# axiom_beta_sensor_cmv12000_tht_v0_16_r1_.net
KiCad netlist of a schematic drawn in EAGLE
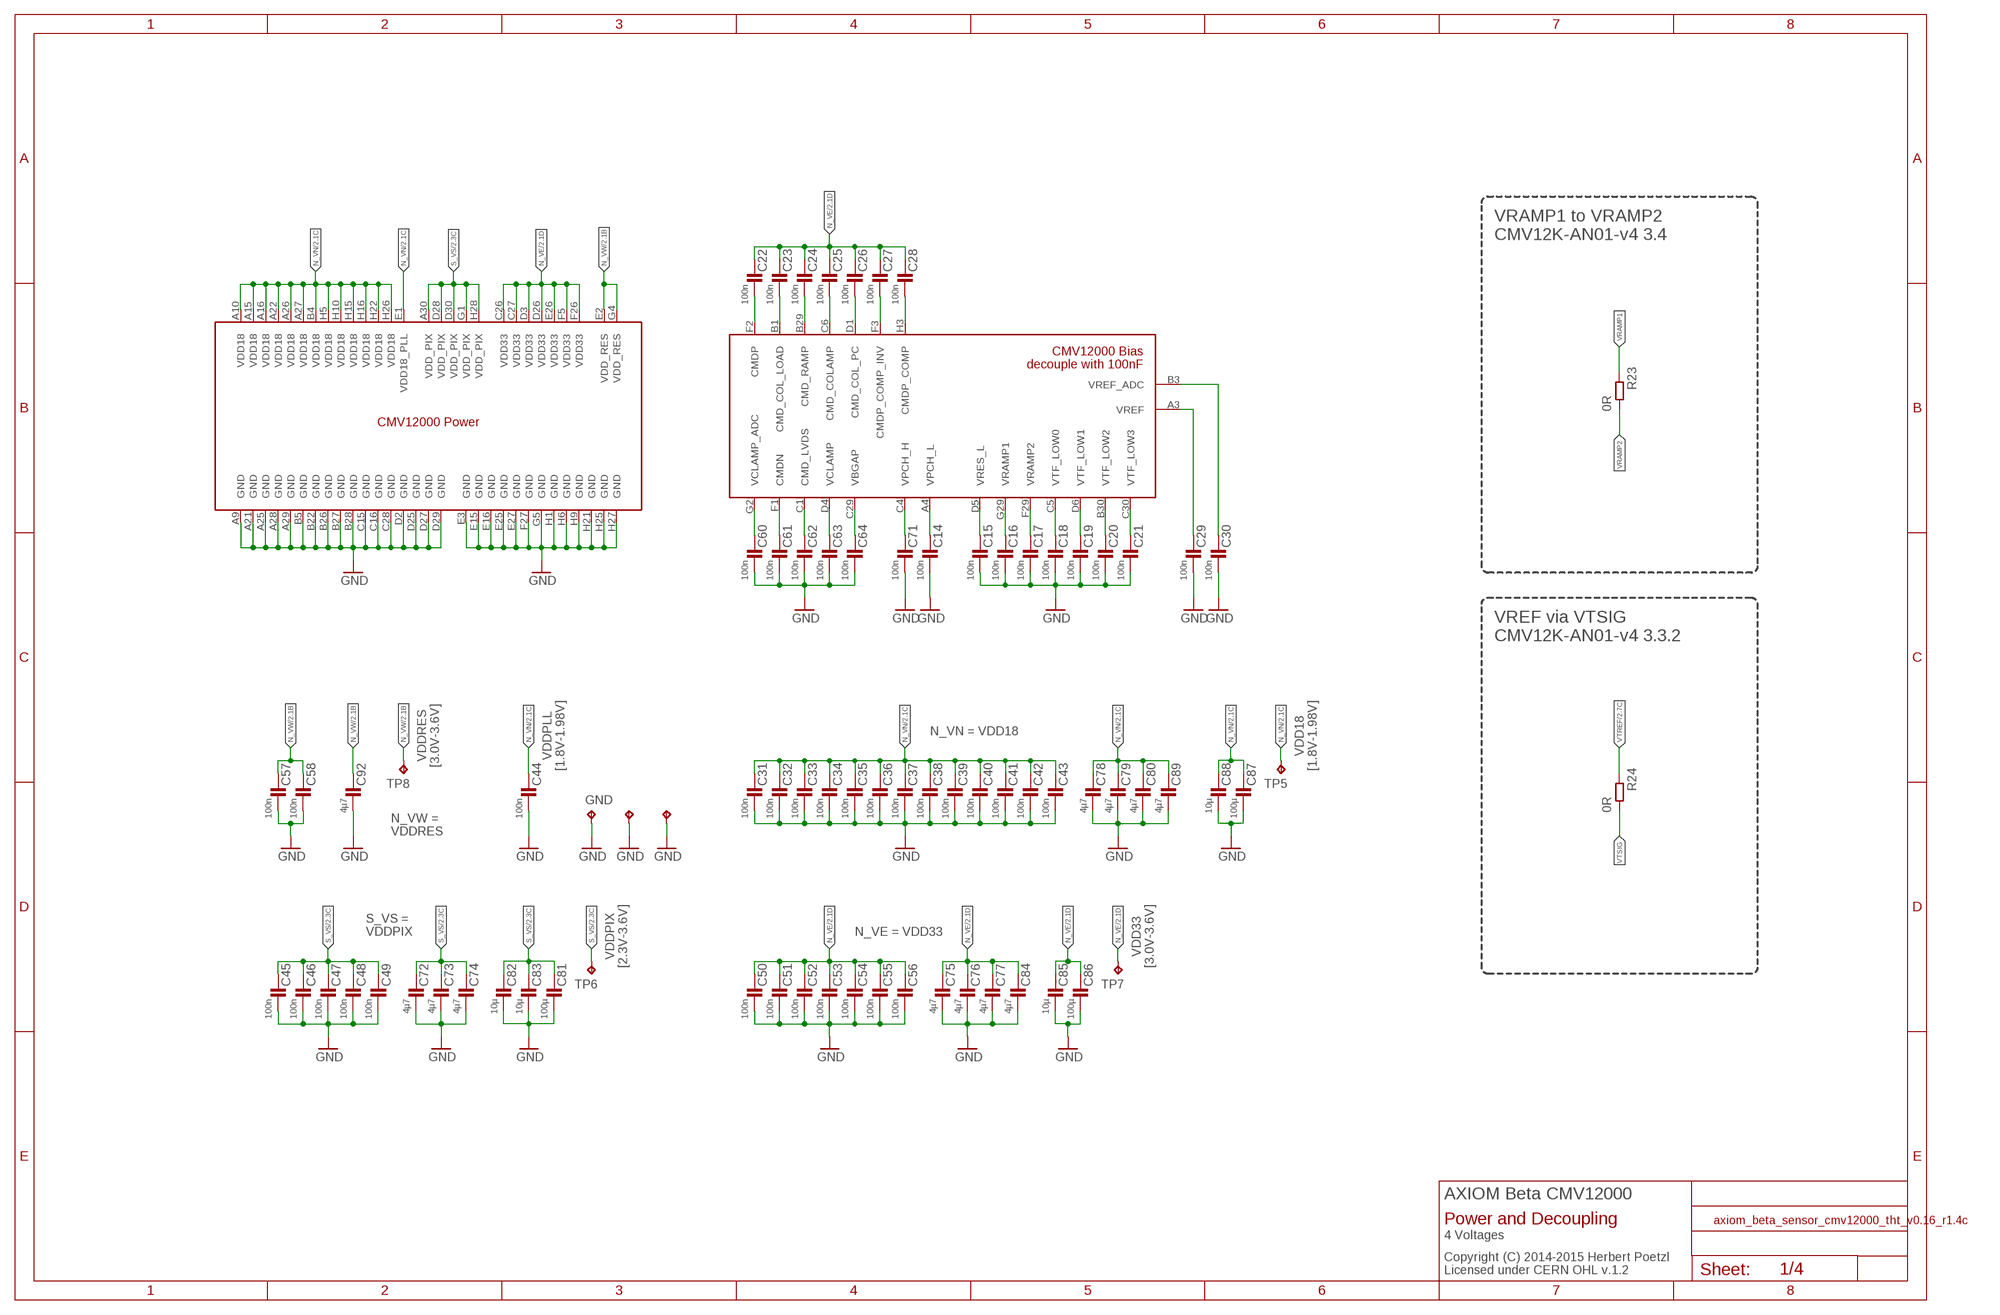
[diagram p0: schematic, sheet 1]
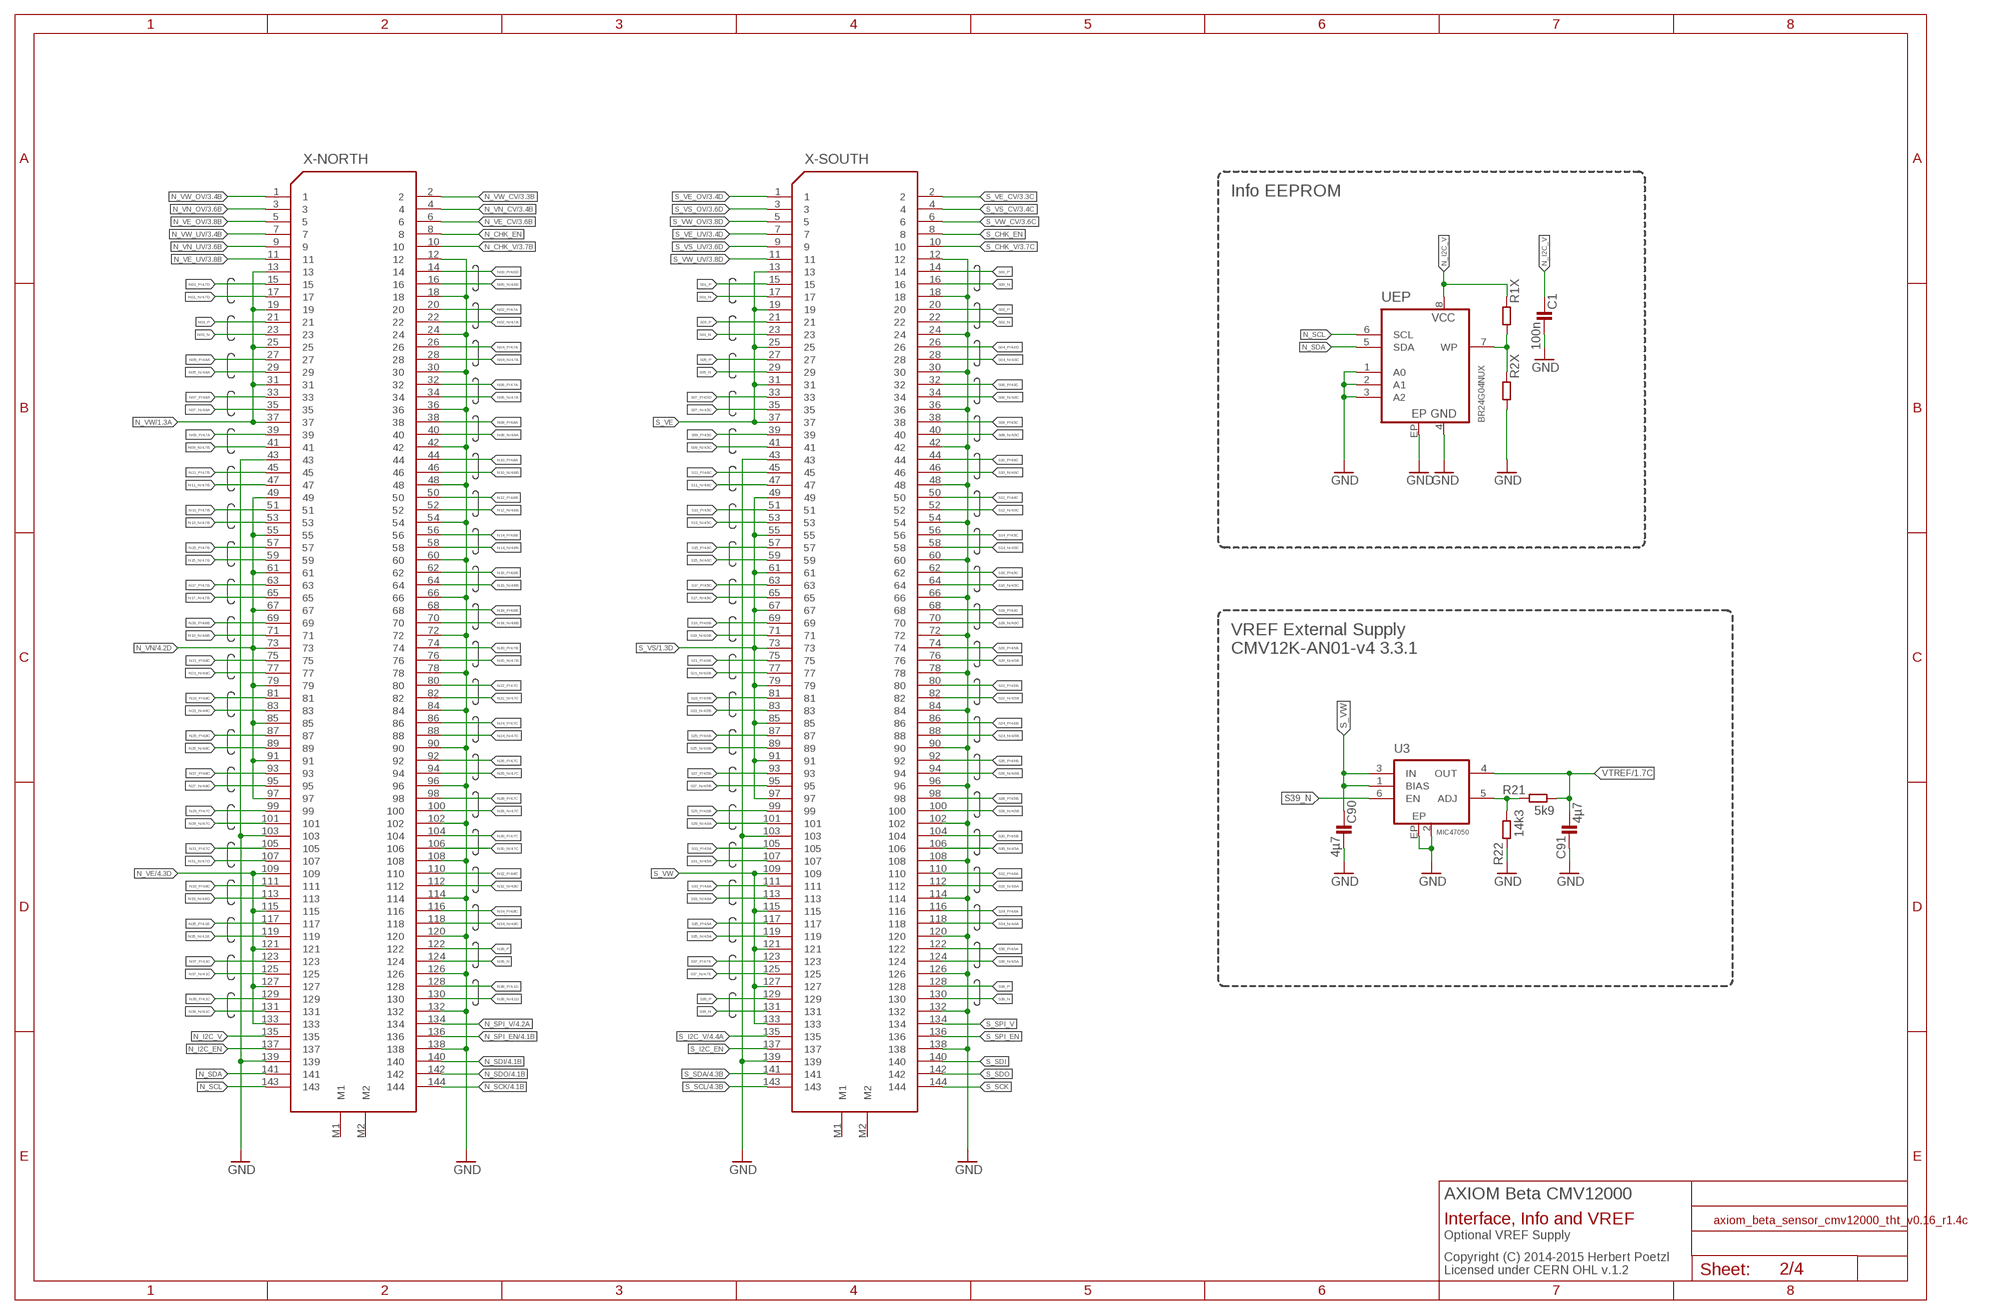
[diagram p1: schematic, sheet 2]
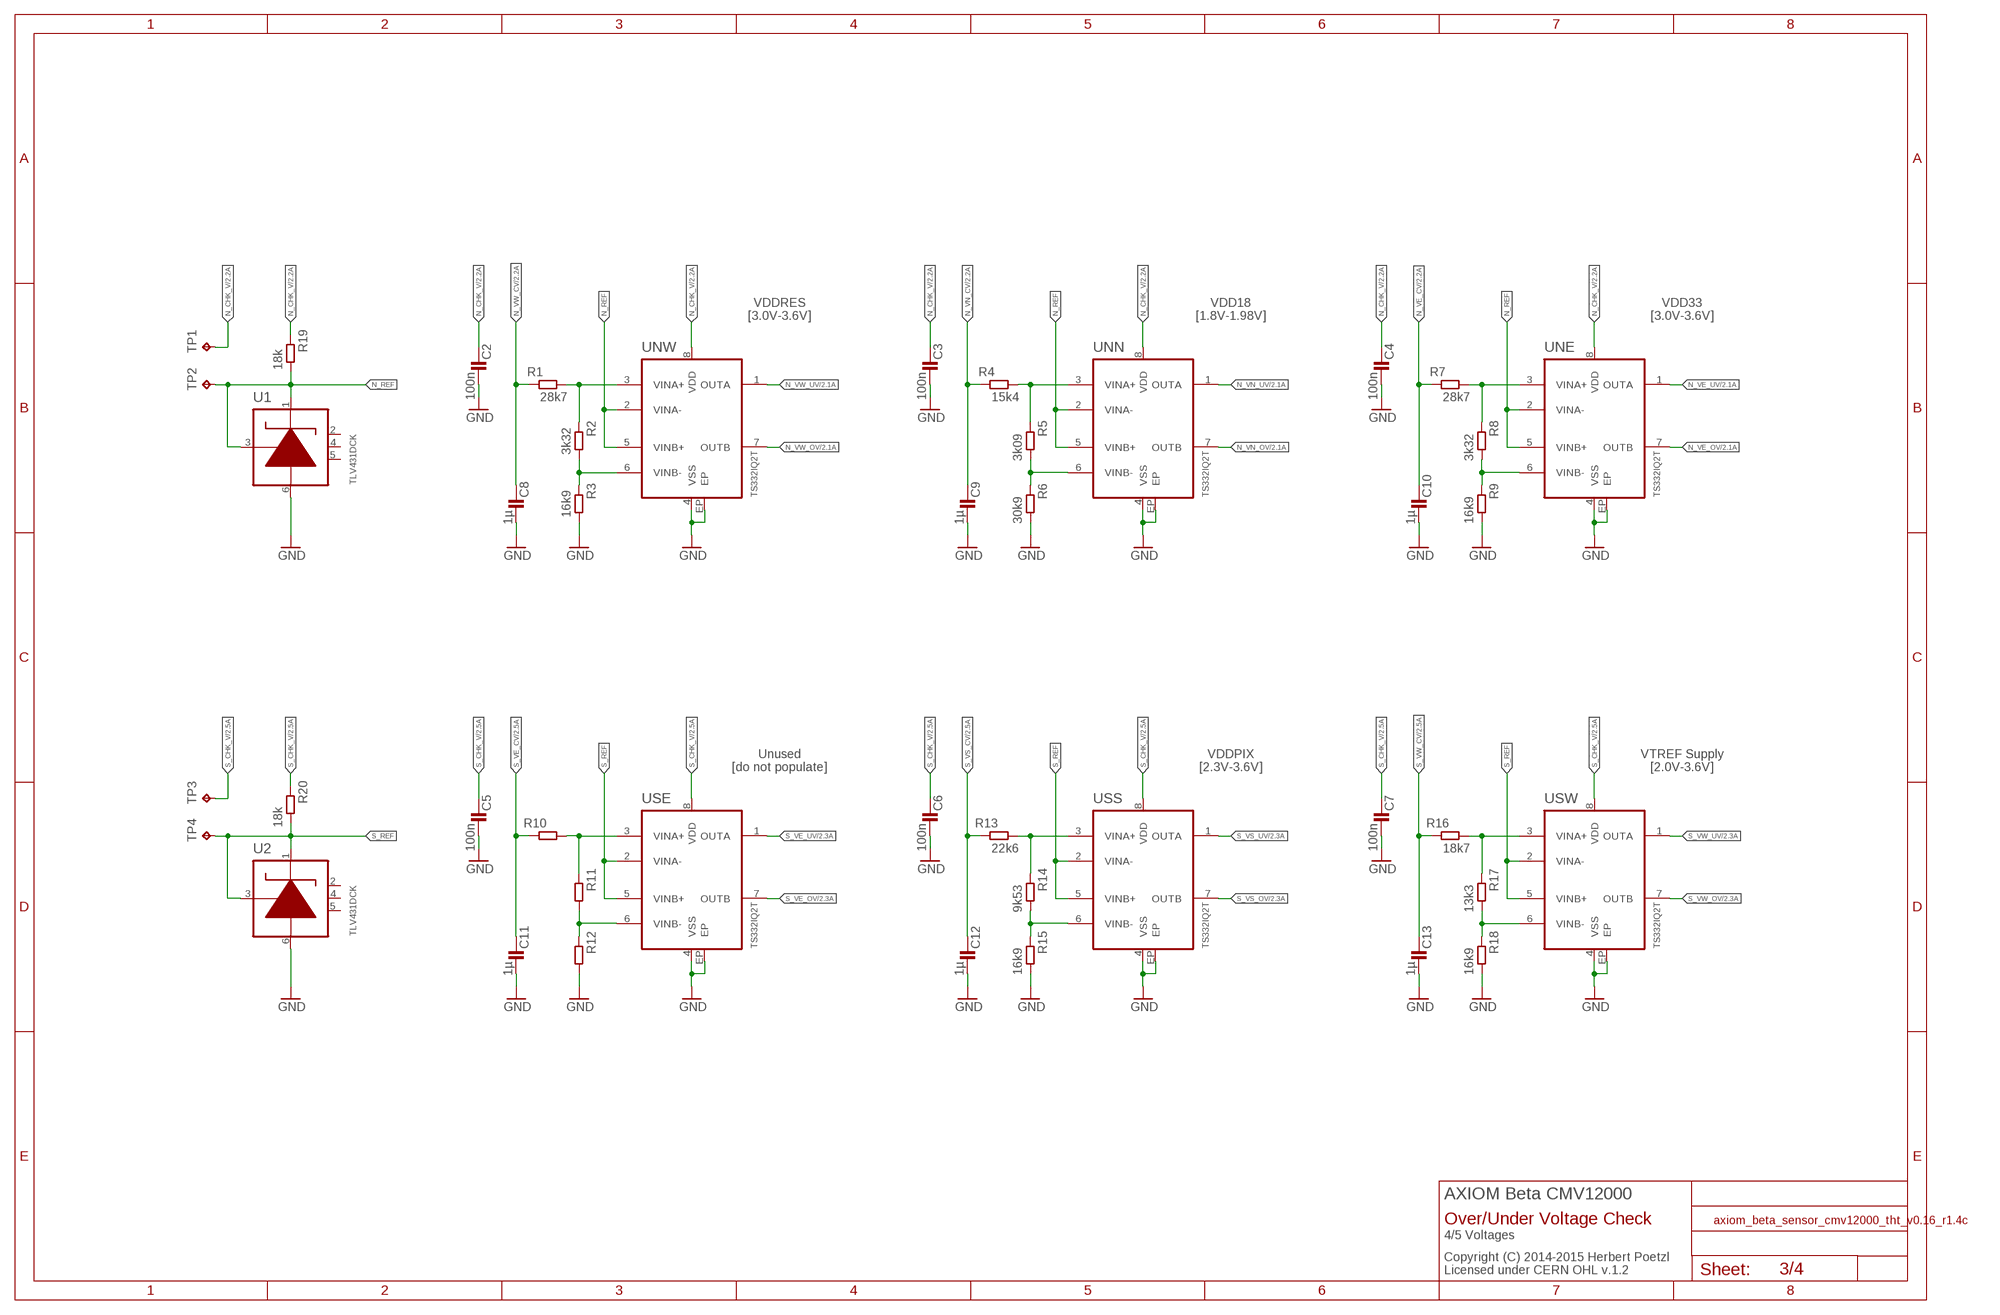
[diagram p2: schematic, sheet 3]
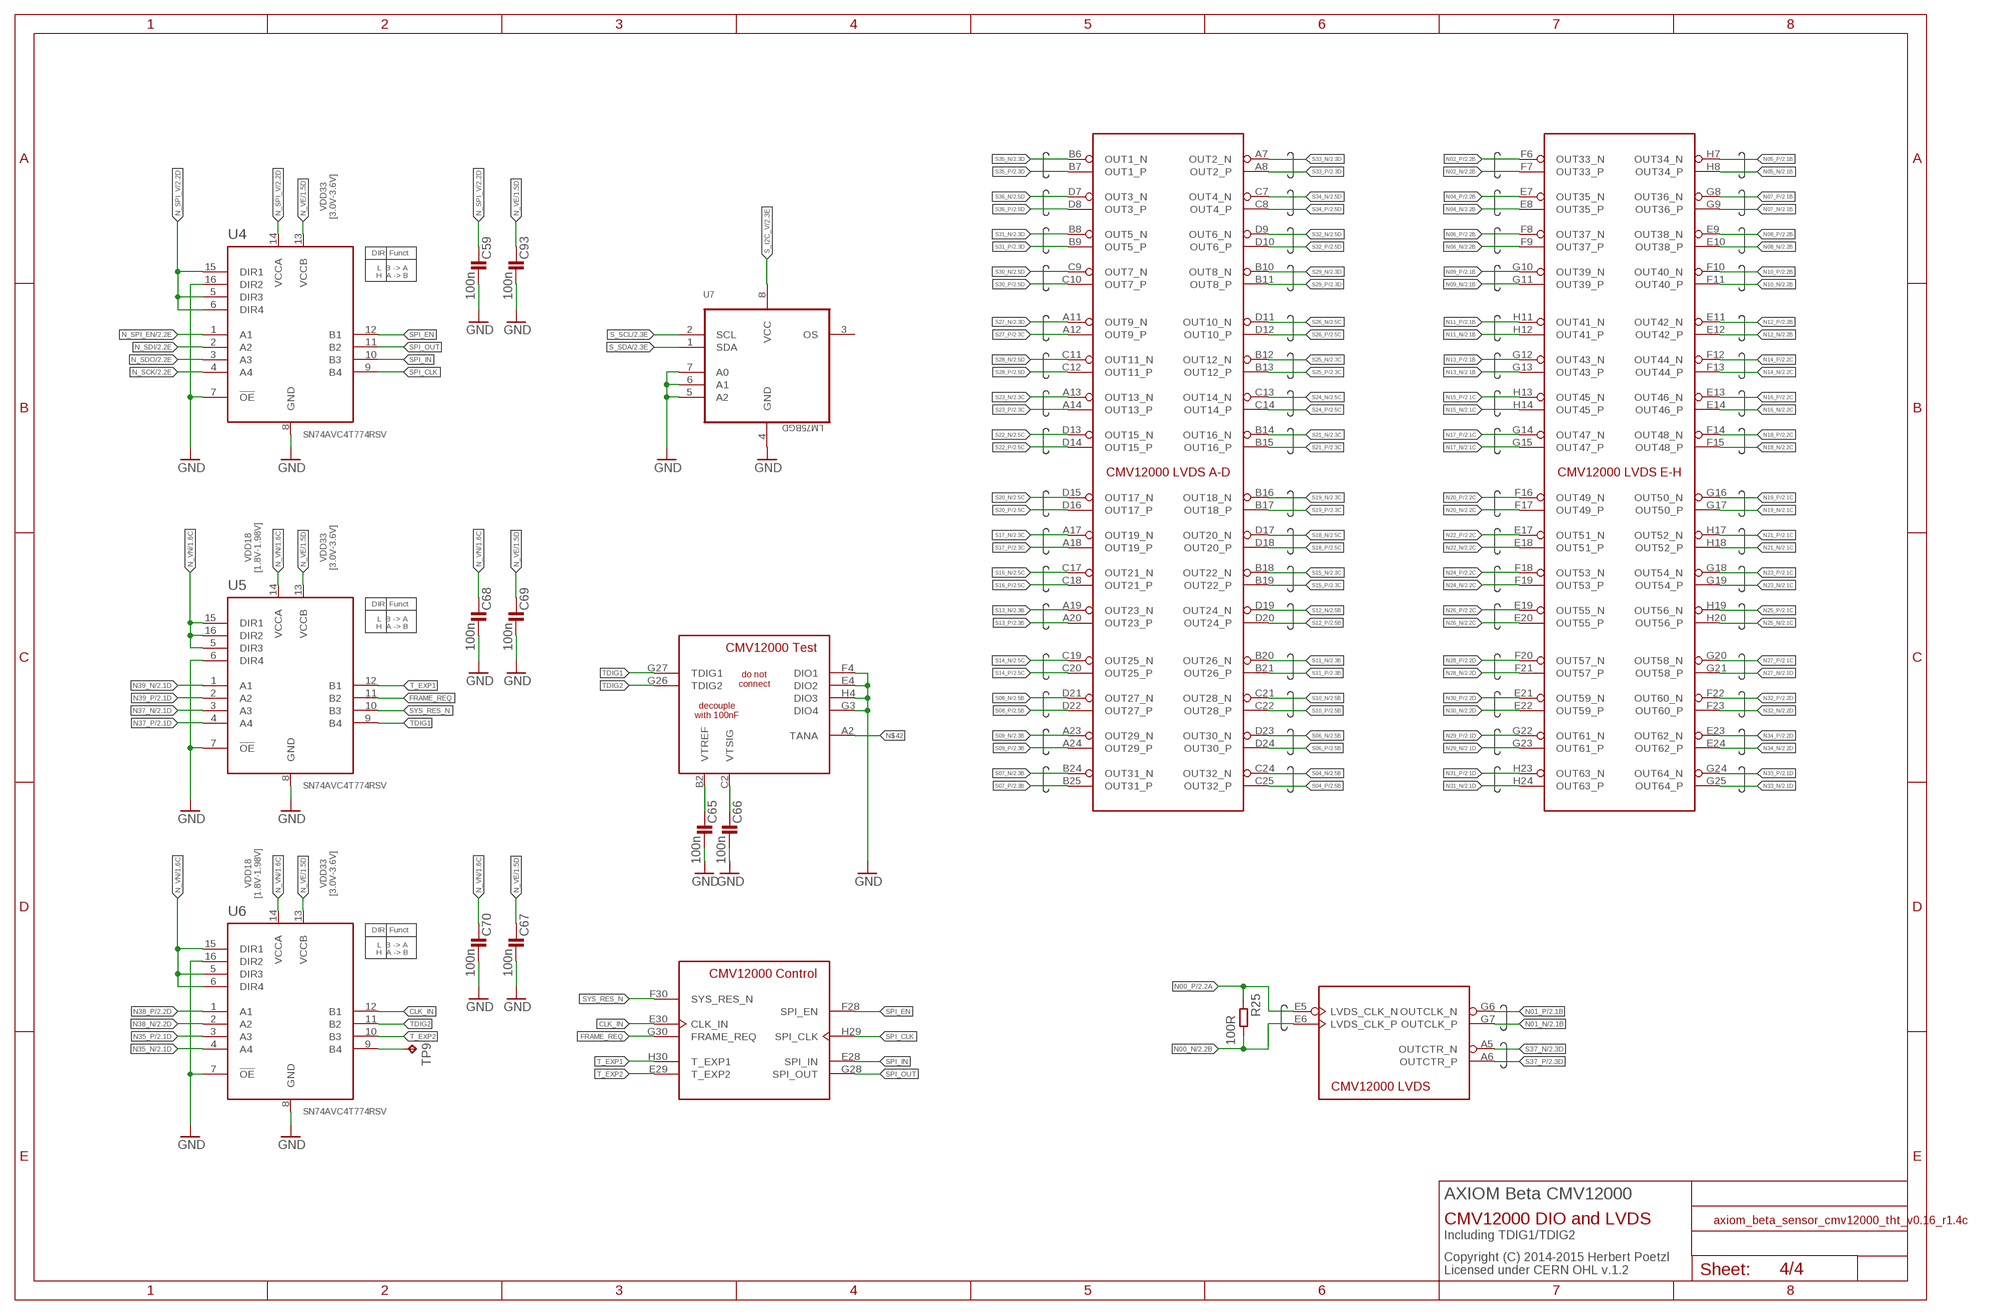
[diagram p3: schematic, sheet 4]

(export (version "E")
  (design (tool "Eeschema 10.0.6"))
  (components
    (comp (ref "C1")
      (value "100n")
      (footprint "eagle-import:0402-C")
      (libsource (lib "eagle-import") (part "C0402-C"))
    )
    (comp (ref "C90")
      (value "4µ7")
      (footprint "eagle-import:0402-C")
      (libsource (lib "eagle-import") (part "C0402-C"))
    )
    (comp (ref "C91")
      (value "4µ7")
      (footprint "eagle-import:0402-C")
      (libsource (lib "eagle-import") (part "C0402-C"))
    )
    (comp (ref "R1X")
      (value "R0402-C")
      (footprint "eagle-import:0402-C")
      (libsource (lib "eagle-import") (part "R0402-C"))
    )
    (comp (ref "R2X")
      (value "R0402-C")
      (footprint "eagle-import:0402-C")
      (libsource (lib "eagle-import") (part "R0402-C"))
    )
    (comp (ref "R21")
      (value "5k9")
      (footprint "eagle-import:0402-C")
      (libsource (lib "eagle-import") (part "R0402-C"))
    )
    (comp (ref "R22")
      (value "14k3")
      (footprint "eagle-import:0402-C")
      (libsource (lib "eagle-import") (part "R0402-C"))
    )
    (comp (ref "U3")
      (value "MIC47050")
      (footprint "eagle-import:MLF-6")
      (libsource (lib "eagle-import") (part "MIC47050-ADJ"))
    )
    (comp (ref "UEP")
      (value "BR24G04NUX")
      (footprint "eagle-import:DFN200X300X100-9N")
      (libsource (lib "eagle-import") (part "BR24G04NUX"))
    )
    (comp (ref "X-NORTH")
      (value "FX10-144P")
      (footprint "eagle-import:FX10A-144P")
      (libsource (lib "eagle-import") (part "FX10-144P"))
    )
    (comp (ref "X-SOUTH")
      (value "FX10-144P")
      (footprint "eagle-import:FX10A-144P")
      (libsource (lib "eagle-import") (part "FX10-144P"))
    )
    (comp (ref "C59")
      (value "100n")
      (footprint "eagle-import:0402-C")
      (libsource (lib "eagle-import") (part "C0402-C"))
    )
    (comp (ref "C65")
      (value "100n")
      (footprint "eagle-import:0402-C")
      (libsource (lib "eagle-import") (part "C0402-C"))
    )
    (comp (ref "C66")
      (value "100n")
      (footprint "eagle-import:0402-C")
      (libsource (lib "eagle-import") (part "C0402-C"))
    )
    (comp (ref "C67")
      (value "100n")
      (footprint "eagle-import:0402-C")
      (libsource (lib "eagle-import") (part "C0402-C"))
    )
    (comp (ref "C68")
      (value "100n")
      (footprint "eagle-import:0402-C")
      (libsource (lib "eagle-import") (part "C0402-C"))
    )
    (comp (ref "C69")
      (value "100n")
      (footprint "eagle-import:0402-C")
      (libsource (lib "eagle-import") (part "C0402-C"))
    )
    (comp (ref "C70")
      (value "100n")
      (footprint "eagle-import:0402-C")
      (libsource (lib "eagle-import") (part "C0402-C"))
    )
    (comp (ref "C93")
      (value "100n")
      (footprint "eagle-import:0402-C")
      (libsource (lib "eagle-import") (part "C0402-C"))
    )
    (comp (ref "R25")
      (value "100R")
      (footprint "eagle-import:0402-C")
      (libsource (lib "eagle-import") (part "R0402-C"))
    )
    (comp (ref "SENSOR")
      (value "CMV12000ANDON")
      (footprint "eagle-import:10-30-07-237-400T4")
      (libsource (lib "eagle-import") (part "CMV12000ANDON"))
    )
    (comp (ref "TP9")
      (value "TPTP10R")
      (footprint "eagle-import:TP10R")
      (libsource (lib "eagle-import") (part "TPTP10R"))
    )
    (comp (ref "U4")
      (value "SN74AVC4T774RSV")
      (footprint "eagle-import:QFN40P185X265X55-16N")
      (libsource (lib "eagle-import") (part "SN74AVC4T774RSV"))
    )
    (comp (ref "U5")
      (value "SN74AVC4T774RSV")
      (footprint "eagle-import:QFN40P185X265X55-16N")
      (libsource (lib "eagle-import") (part "SN74AVC4T774RSV"))
    )
    (comp (ref "U6")
      (value "SN74AVC4T774RSV")
      (footprint "eagle-import:QFN40P185X265X55-16N")
      (libsource (lib "eagle-import") (part "SN74AVC4T774RSV"))
    )
    (comp (ref "U7")
      (value "LM75BGD")
      (footprint "eagle-import:SOT996-2_3")
      (libsource (lib "eagle-import") (part "LM75BGD"))
    )
    (comp (ref "C2")
      (value "100n")
      (footprint "eagle-import:0402-C")
      (libsource (lib "eagle-import") (part "C0402-C"))
    )
    (comp (ref "C3")
      (value "100n")
      (footprint "eagle-import:0402-C")
      (libsource (lib "eagle-import") (part "C0402-C"))
    )
    (comp (ref "C4")
      (value "100n")
      (footprint "eagle-import:0402-C")
      (libsource (lib "eagle-import") (part "C0402-C"))
    )
    (comp (ref "C5")
      (value "100n")
      (footprint "eagle-import:0402-C")
      (libsource (lib "eagle-import") (part "C0402-C"))
    )
    (comp (ref "C6")
      (value "100n")
      (footprint "eagle-import:0402-C")
      (libsource (lib "eagle-import") (part "C0402-C"))
    )
    (comp (ref "C7")
      (value "100n")
      (footprint "eagle-import:0402-C")
      (libsource (lib "eagle-import") (part "C0402-C"))
    )
    (comp (ref "C8")
      (value "1µ")
      (footprint "eagle-import:0402-C")
      (libsource (lib "eagle-import") (part "C0402-C"))
    )
    (comp (ref "C9")
      (value "1µ")
      (footprint "eagle-import:0402-C")
      (libsource (lib "eagle-import") (part "C0402-C"))
    )
    (comp (ref "C10")
      (value "1µ")
      (footprint "eagle-import:0402-C")
      (libsource (lib "eagle-import") (part "C0402-C"))
    )
    (comp (ref "C11")
      (value "1µ")
      (footprint "eagle-import:0402-C")
      (libsource (lib "eagle-import") (part "C0402-C"))
    )
    (comp (ref "C12")
      (value "1µ")
      (footprint "eagle-import:0402-C")
      (libsource (lib "eagle-import") (part "C0402-C"))
    )
    (comp (ref "C13")
      (value "1µ")
      (footprint "eagle-import:0402-C")
      (libsource (lib "eagle-import") (part "C0402-C"))
    )
    (comp (ref "R1")
      (value "28k7")
      (footprint "eagle-import:0402-C")
      (libsource (lib "eagle-import") (part "R0402-C"))
    )
    (comp (ref "R2")
      (value "3k32")
      (footprint "eagle-import:0402-C")
      (libsource (lib "eagle-import") (part "R0402-C"))
    )
    (comp (ref "R3")
      (value "16k9")
      (footprint "eagle-import:0402-C")
      (libsource (lib "eagle-import") (part "R0402-C"))
    )
    (comp (ref "R4")
      (value "15k4")
      (footprint "eagle-import:0402-C")
      (libsource (lib "eagle-import") (part "R0402-C"))
    )
    (comp (ref "R5")
      (value "3k09")
      (footprint "eagle-import:0402-C")
      (libsource (lib "eagle-import") (part "R0402-C"))
    )
    (comp (ref "R6")
      (value "30k9")
      (footprint "eagle-import:0402-C")
      (libsource (lib "eagle-import") (part "R0402-C"))
    )
    (comp (ref "R7")
      (value "28k7")
      (footprint "eagle-import:0402-C")
      (libsource (lib "eagle-import") (part "R0402-C"))
    )
    (comp (ref "R8")
      (value "3k32")
      (footprint "eagle-import:0402-C")
      (libsource (lib "eagle-import") (part "R0402-C"))
    )
    (comp (ref "R9")
      (value "16k9")
      (footprint "eagle-import:0402-C")
      (libsource (lib "eagle-import") (part "R0402-C"))
    )
    (comp (ref "R10")
      (value "R0402-C")
      (footprint "eagle-import:0402-C")
      (libsource (lib "eagle-import") (part "R0402-C"))
    )
    (comp (ref "R11")
      (value "R0402-C")
      (footprint "eagle-import:0402-C")
      (libsource (lib "eagle-import") (part "R0402-C"))
    )
    (comp (ref "R12")
      (value "R0402-C")
      (footprint "eagle-import:0402-C")
      (libsource (lib "eagle-import") (part "R0402-C"))
    )
    (comp (ref "R13")
      (value "22k6")
      (footprint "eagle-import:0402-C")
      (libsource (lib "eagle-import") (part "R0402-C"))
    )
    (comp (ref "R14")
      (value "9k53")
      (footprint "eagle-import:0402-C")
      (libsource (lib "eagle-import") (part "R0402-C"))
    )
    (comp (ref "R15")
      (value "16k9")
      (footprint "eagle-import:0402-C")
      (libsource (lib "eagle-import") (part "R0402-C"))
    )
    (comp (ref "R16")
      (value "18k7")
      (footprint "eagle-import:0402-C")
      (libsource (lib "eagle-import") (part "R0402-C"))
    )
    (comp (ref "R17")
      (value "13k3")
      (footprint "eagle-import:0402-C")
      (libsource (lib "eagle-import") (part "R0402-C"))
    )
    (comp (ref "R18")
      (value "16k9")
      (footprint "eagle-import:0402-C")
      (libsource (lib "eagle-import") (part "R0402-C"))
    )
    (comp (ref "R19")
      (value "18k")
      (footprint "eagle-import:0402-C")
      (libsource (lib "eagle-import") (part "R0402-C"))
    )
    (comp (ref "R20")
      (value "18k")
      (footprint "eagle-import:0402-C")
      (libsource (lib "eagle-import") (part "R0402-C"))
    )
    (comp (ref "TP1")
      (value "TPTP10R")
      (footprint "eagle-import:TP10R")
      (libsource (lib "eagle-import") (part "TPTP10R"))
    )
    (comp (ref "TP2")
      (value "TPTP10R")
      (footprint "eagle-import:TP10R")
      (libsource (lib "eagle-import") (part "TPTP10R"))
    )
    (comp (ref "TP3")
      (value "TPTP10R")
      (footprint "eagle-import:TP10R")
      (libsource (lib "eagle-import") (part "TPTP10R"))
    )
    (comp (ref "TP4")
      (value "TPTP10R")
      (footprint "eagle-import:TP10R")
      (libsource (lib "eagle-import") (part "TPTP10R"))
    )
    (comp (ref "U1")
      (value "TLV431DCK")
      (footprint "eagle-import:SOT65P210X110-6N")
      (libsource (lib "eagle-import") (part "TLV431DCK"))
    )
    (comp (ref "U2")
      (value "TLV431DCK")
      (footprint "eagle-import:SOT65P210X110-6N")
      (libsource (lib "eagle-import") (part "TLV431DCK"))
    )
    (comp (ref "UNE")
      (value "TS332IQ2T")
      (footprint "eagle-import:DFN200X200X100-9N")
      (libsource (lib "eagle-import") (part "TS332IQ2T"))
    )
    (comp (ref "UNN")
      (value "TS332IQ2T")
      (footprint "eagle-import:DFN200X200X100-9N")
      (libsource (lib "eagle-import") (part "TS332IQ2T"))
    )
    (comp (ref "UNW")
      (value "TS332IQ2T")
      (footprint "eagle-import:DFN200X200X100-9N")
      (libsource (lib "eagle-import") (part "TS332IQ2T"))
    )
    (comp (ref "USE")
      (value "TS332IQ2T")
      (footprint "eagle-import:DFN200X200X100-9N")
      (libsource (lib "eagle-import") (part "TS332IQ2T"))
    )
    (comp (ref "USS")
      (value "TS332IQ2T")
      (footprint "eagle-import:DFN200X200X100-9N")
      (libsource (lib "eagle-import") (part "TS332IQ2T"))
    )
    (comp (ref "USW")
      (value "TS332IQ2T")
      (footprint "eagle-import:DFN200X200X100-9N")
      (libsource (lib "eagle-import") (part "TS332IQ2T"))
    )
    (comp (ref "C14")
      (value "100n")
      (footprint "eagle-import:0402-C")
      (libsource (lib "eagle-import") (part "C0402-C"))
    )
    (comp (ref "C15")
      (value "100n")
      (footprint "eagle-import:0402-C")
      (libsource (lib "eagle-import") (part "C0402-C"))
    )
    (comp (ref "C16")
      (value "100n")
      (footprint "eagle-import:0402-C")
      (libsource (lib "eagle-import") (part "C0402-C"))
    )
    (comp (ref "C17")
      (value "100n")
      (footprint "eagle-import:0402-C")
      (libsource (lib "eagle-import") (part "C0402-C"))
    )
    (comp (ref "C18")
      (value "100n")
      (footprint "eagle-import:0402-C")
      (libsource (lib "eagle-import") (part "C0402-C"))
    )
    (comp (ref "C19")
      (value "100n")
      (footprint "eagle-import:0402-C")
      (libsource (lib "eagle-import") (part "C0402-C"))
    )
    (comp (ref "C20")
      (value "100n")
      (footprint "eagle-import:0402-C")
      (libsource (lib "eagle-import") (part "C0402-C"))
    )
    (comp (ref "C21")
      (value "100n")
      (footprint "eagle-import:0402-C")
      (libsource (lib "eagle-import") (part "C0402-C"))
    )
    (comp (ref "C22")
      (value "100n")
      (footprint "eagle-import:0402-C")
      (libsource (lib "eagle-import") (part "C0402-C"))
    )
    (comp (ref "C23")
      (value "100n")
      (footprint "eagle-import:0402-C")
      (libsource (lib "eagle-import") (part "C0402-C"))
    )
    (comp (ref "C24")
      (value "100n")
      (footprint "eagle-import:0402-C")
      (libsource (lib "eagle-import") (part "C0402-C"))
    )
    (comp (ref "C25")
      (value "100n")
      (footprint "eagle-import:0402-C")
      (libsource (lib "eagle-import") (part "C0402-C"))
    )
    (comp (ref "C26")
      (value "100n")
      (footprint "eagle-import:0402-C")
      (libsource (lib "eagle-import") (part "C0402-C"))
    )
    (comp (ref "C27")
      (value "100n")
      (footprint "eagle-import:0402-C")
      (libsource (lib "eagle-import") (part "C0402-C"))
    )
    (comp (ref "C28")
      (value "100n")
      (footprint "eagle-import:0402-C")
      (libsource (lib "eagle-import") (part "C0402-C"))
    )
    (comp (ref "C29")
      (value "100n")
      (footprint "eagle-import:0402-C")
      (libsource (lib "eagle-import") (part "C0402-C"))
    )
    (comp (ref "C30")
      (value "100n")
      (footprint "eagle-import:0402-C")
      (libsource (lib "eagle-import") (part "C0402-C"))
    )
    (comp (ref "C31")
      (value "100n")
      (footprint "eagle-import:0402-C")
      (libsource (lib "eagle-import") (part "C0402-C"))
    )
    (comp (ref "C32")
      (value "100n")
      (footprint "eagle-import:0402-C")
      (libsource (lib "eagle-import") (part "C0402-C"))
    )
    (comp (ref "C33")
      (value "100n")
      (footprint "eagle-import:0402-C")
      (libsource (lib "eagle-import") (part "C0402-C"))
    )
    (comp (ref "C34")
      (value "100n")
      (footprint "eagle-import:0402-C")
      (libsource (lib "eagle-import") (part "C0402-C"))
    )
    (comp (ref "C35")
      (value "100n")
      (footprint "eagle-import:0402-C")
      (libsource (lib "eagle-import") (part "C0402-C"))
    )
    (comp (ref "C36")
      (value "100n")
      (footprint "eagle-import:0402-C")
      (libsource (lib "eagle-import") (part "C0402-C"))
    )
    (comp (ref "C37")
      (value "100n")
      (footprint "eagle-import:0402-C")
      (libsource (lib "eagle-import") (part "C0402-C"))
    )
    (comp (ref "C38")
      (value "100n")
      (footprint "eagle-import:0402-C")
      (libsource (lib "eagle-import") (part "C0402-C"))
    )
    (comp (ref "C39")
      (value "100n")
      (footprint "eagle-import:0402-C")
      (libsource (lib "eagle-import") (part "C0402-C"))
    )
    (comp (ref "C40")
      (value "100n")
      (footprint "eagle-import:0402-C")
      (libsource (lib "eagle-import") (part "C0402-C"))
    )
    (comp (ref "C41")
      (value "100n")
      (footprint "eagle-import:0402-C")
      (libsource (lib "eagle-import") (part "C0402-C"))
    )
    (comp (ref "C42")
      (value "100n")
      (footprint "eagle-import:0402-C")
      (libsource (lib "eagle-import") (part "C0402-C"))
    )
    (comp (ref "C43")
      (value "100n")
      (footprint "eagle-import:0402-C")
      (libsource (lib "eagle-import") (part "C0402-C"))
    )
    (comp (ref "C44")
      (value "100n")
      (footprint "eagle-import:0402-C")
      (libsource (lib "eagle-import") (part "C0402-C"))
    )
    (comp (ref "C45")
      (value "100n")
      (footprint "eagle-import:0402-C")
      (libsource (lib "eagle-import") (part "C0402-C"))
    )
    (comp (ref "C46")
      (value "100n")
      (footprint "eagle-import:0402-C")
      (libsource (lib "eagle-import") (part "C0402-C"))
    )
    (comp (ref "C47")
      (value "100n")
      (footprint "eagle-import:0402-C")
      (libsource (lib "eagle-import") (part "C0402-C"))
    )
    (comp (ref "C48")
      (value "100n")
      (footprint "eagle-import:0402-C")
      (libsource (lib "eagle-import") (part "C0402-C"))
    )
    (comp (ref "C49")
      (value "100n")
      (footprint "eagle-import:0402-C")
      (libsource (lib "eagle-import") (part "C0402-C"))
    )
    (comp (ref "C50")
      (value "100n")
      (footprint "eagle-import:0402-C")
      (libsource (lib "eagle-import") (part "C0402-C"))
    )
    (comp (ref "C51")
      (value "100n")
      (footprint "eagle-import:0402-C")
      (libsource (lib "eagle-import") (part "C0402-C"))
    )
    (comp (ref "C52")
      (value "100n")
      (footprint "eagle-import:0402-C")
      (libsource (lib "eagle-import") (part "C0402-C"))
    )
    (comp (ref "C53")
      (value "100n")
      (footprint "eagle-import:0402-C")
      (libsource (lib "eagle-import") (part "C0402-C"))
    )
    (comp (ref "C54")
      (value "100n")
      (footprint "eagle-import:0402-C")
      (libsource (lib "eagle-import") (part "C0402-C"))
    )
    (comp (ref "C55")
      (value "100n")
      (footprint "eagle-import:0402-C")
      (libsource (lib "eagle-import") (part "C0402-C"))
    )
    (comp (ref "C56")
      (value "100n")
      (footprint "eagle-import:0402-C")
      (libsource (lib "eagle-import") (part "C0402-C"))
    )
    (comp (ref "C57")
      (value "100n")
      (footprint "eagle-import:0402-C")
      (libsource (lib "eagle-import") (part "C0402-C"))
    )
    (comp (ref "C58")
      (value "100n")
      (footprint "eagle-import:0402-C")
      (libsource (lib "eagle-import") (part "C0402-C"))
    )
    (comp (ref "C60")
      (value "100n")
      (footprint "eagle-import:0402-C")
      (libsource (lib "eagle-import") (part "C0402-C"))
    )
    (comp (ref "C61")
      (value "100n")
      (footprint "eagle-import:0402-C")
      (libsource (lib "eagle-import") (part "C0402-C"))
    )
    (comp (ref "C62")
      (value "100n")
      (footprint "eagle-import:0402-C")
      (libsource (lib "eagle-import") (part "C0402-C"))
    )
    (comp (ref "C63")
      (value "100n")
      (footprint "eagle-import:0402-C")
      (libsource (lib "eagle-import") (part "C0402-C"))
    )
    (comp (ref "C64")
      (value "100n")
      (footprint "eagle-import:0402-C")
      (libsource (lib "eagle-import") (part "C0402-C"))
    )
    (comp (ref "C71")
      (value "100n")
      (footprint "eagle-import:0402-C")
      (libsource (lib "eagle-import") (part "C0402-C"))
    )
    (comp (ref "C72")
      (value "4µ7")
      (footprint "eagle-import:0402-B")
      (libsource (lib "eagle-import") (part "C0402-B"))
    )
    (comp (ref "C73")
      (value "4µ7")
      (footprint "eagle-import:0402-C")
      (libsource (lib "eagle-import") (part "C0402-C"))
    )
    (comp (ref "C74")
      (value "4µ7")
      (footprint "eagle-import:0402-C")
      (libsource (lib "eagle-import") (part "C0402-C"))
    )
    (comp (ref "C75")
      (value "4µ7")
      (footprint "eagle-import:0402-C")
      (libsource (lib "eagle-import") (part "C0402-C"))
    )
    (comp (ref "C76")
      (value "4µ7")
      (footprint "eagle-import:0402-C")
      (libsource (lib "eagle-import") (part "C0402-C"))
    )
    (comp (ref "C77")
      (value "4µ7")
      (footprint "eagle-import:0402-B")
      (libsource (lib "eagle-import") (part "C0402-B"))
    )
    (comp (ref "C78")
      (value "4µ7")
      (footprint "eagle-import:0402-B")
      (libsource (lib "eagle-import") (part "C0402-B"))
    )
    (comp (ref "C79")
      (value "4µ7")
      (footprint "eagle-import:0402-C")
      (libsource (lib "eagle-import") (part "C0402-C"))
    )
    (comp (ref "C80")
      (value "4µ7")
      (footprint "eagle-import:0402-C")
      (libsource (lib "eagle-import") (part "C0402-C"))
    )
    (comp (ref "C81")
      (value "100µ")
      (footprint "eagle-import:1206-B")
      (libsource (lib "eagle-import") (part "C1206-B"))
    )
    (comp (ref "C82")
      (value "10µ")
      (footprint "eagle-import:0603-C")
      (libsource (lib "eagle-import") (part "C0603-C"))
    )
    (comp (ref "C83")
      (value "10µ")
      (footprint "eagle-import:0603-C")
      (libsource (lib "eagle-import") (part "C0603-C"))
    )
    (comp (ref "C84")
      (value "4µ7")
      (footprint "eagle-import:0402-C")
      (libsource (lib "eagle-import") (part "C0402-C"))
    )
    (comp (ref "C85")
      (value "10µ")
      (footprint "eagle-import:0603-C")
      (libsource (lib "eagle-import") (part "C0603-C"))
    )
    (comp (ref "C86")
      (value "100µ")
      (footprint "eagle-import:1206-B")
      (libsource (lib "eagle-import") (part "C1206-B"))
    )
    (comp (ref "C87")
      (value "100µ")
      (footprint "eagle-import:1206-B")
      (libsource (lib "eagle-import") (part "C1206-B"))
    )
    (comp (ref "C88")
      (value "10µ")
      (footprint "eagle-import:0603-C")
      (libsource (lib "eagle-import") (part "C0603-C"))
    )
    (comp (ref "C89")
      (value "4µ7")
      (footprint "eagle-import:0402-C")
      (libsource (lib "eagle-import") (part "C0402-C"))
    )
    (comp (ref "C92")
      (value "4µ7")
      (footprint "eagle-import:0402-C")
      (libsource (lib "eagle-import") (part "C0402-C"))
    )
    (comp (ref "GND")
      (value "TPTP10R")
      (footprint "eagle-import:TP10R")
      (libsource (lib "eagle-import") (part "TPTP10R"))
    )
    (comp (ref "GND75")
      (value "TPTP10R")
      (footprint "eagle-import:TP10R")
      (libsource (lib "eagle-import") (part "TPTP10R"))
    )
    (comp (ref "GND77")
      (value "TPTP10R")
      (footprint "eagle-import:TP10R")
      (libsource (lib "eagle-import") (part "TPTP10R"))
    )
    (comp (ref "R23")
      (value "0R")
      (footprint "eagle-import:0402-C")
      (libsource (lib "eagle-import") (part "R0402-C"))
    )
    (comp (ref "R24")
      (value "0R")
      (footprint "eagle-import:0402-C")
      (libsource (lib "eagle-import") (part "R0402-C"))
    )
    (comp (ref "TP5")
      (value "TPTP10R")
      (footprint "eagle-import:TP10R")
      (libsource (lib "eagle-import") (part "TPTP10R"))
    )
    (comp (ref "TP6")
      (value "TPTP10R")
      (footprint "eagle-import:TP10R")
      (libsource (lib "eagle-import") (part "TPTP10R"))
    )
    (comp (ref "TP7")
      (value "TPTP10R")
      (footprint "eagle-import:TP10R")
      (libsource (lib "eagle-import") (part "TPTP10R"))
    )
    (comp (ref "TP8")
      (value "TPTP10R")
      (footprint "eagle-import:TP10R")
      (libsource (lib "eagle-import") (part "TPTP10R"))
    )
  )
  (nets
    (net (code "1") (name "CLK_IN") (class "Default")
      (node (ref "SENSOR") (pin "E30") (pinfunction "CLK_IN_E30") (pintype "input"))
      (node (ref "U6") (pin "12") (pinfunction "B1_12") (pintype "bidirectional"))
    )
    (net (code "2") (name "FRAME_REQ") (class "Default")
      (node (ref "SENSOR") (pin "G30") (pinfunction "FRAME_REQ_G30") (pintype "input"))
      (node (ref "U5") (pin "11") (pinfunction "B2_11") (pintype "bidirectional"))
    )
    (net (code "3") (name "GND") (class "Default")
      (node (ref "C1") (pin "2") (pinfunction "2_2") (pintype "passive"))
      (node (ref "C10") (pin "2") (pinfunction "2_2") (pintype "passive"))
      (node (ref "C11") (pin "2") (pinfunction "2_2") (pintype "passive"))
      (node (ref "C12") (pin "2") (pinfunction "2_2") (pintype "passive"))
      (node (ref "C13") (pin "2") (pinfunction "2_2") (pintype "passive"))
      (node (ref "C14") (pin "2") (pinfunction "2_2") (pintype "passive"))
      (node (ref "C15") (pin "2") (pinfunction "2_2") (pintype "passive"))
      (node (ref "C16") (pin "2") (pinfunction "2_2") (pintype "passive"))
      (node (ref "C17") (pin "2") (pinfunction "2_2") (pintype "passive"))
      (node (ref "C18") (pin "2") (pinfunction "2_2") (pintype "passive"))
      (node (ref "C19") (pin "2") (pinfunction "2_2") (pintype "passive"))
      (node (ref "C2") (pin "2") (pinfunction "2_2") (pintype "passive"))
      (node (ref "C20") (pin "2") (pinfunction "2_2") (pintype "passive"))
      (node (ref "C21") (pin "2") (pinfunction "2_2") (pintype "passive"))
      (node (ref "C29") (pin "2") (pinfunction "2_2") (pintype "passive"))
      (node (ref "C3") (pin "2") (pinfunction "2_2") (pintype "passive"))
      (node (ref "C30") (pin "2") (pinfunction "2_2") (pintype "passive"))
      (node (ref "C31") (pin "2") (pinfunction "2_2") (pintype "passive"))
      (node (ref "C32") (pin "2") (pinfunction "2_2") (pintype "passive"))
      (node (ref "C33") (pin "2") (pinfunction "2_2") (pintype "passive"))
      (node (ref "C34") (pin "2") (pinfunction "2_2") (pintype "passive"))
      (node (ref "C35") (pin "2") (pinfunction "2_2") (pintype "passive"))
      (node (ref "C36") (pin "2") (pinfunction "2_2") (pintype "passive"))
      (node (ref "C37") (pin "2") (pinfunction "2_2") (pintype "passive"))
      (node (ref "C38") (pin "2") (pinfunction "2_2") (pintype "passive"))
      (node (ref "C39") (pin "2") (pinfunction "2_2") (pintype "passive"))
      (node (ref "C4") (pin "2") (pinfunction "2_2") (pintype "passive"))
      (node (ref "C40") (pin "2") (pinfunction "2_2") (pintype "passive"))
      (node (ref "C41") (pin "2") (pinfunction "2_2") (pintype "passive"))
      (node (ref "C42") (pin "2") (pinfunction "2_2") (pintype "passive"))
      (node (ref "C43") (pin "2") (pinfunction "2_2") (pintype "passive"))
      (node (ref "C44") (pin "2") (pinfunction "2_2") (pintype "passive"))
      (node (ref "C45") (pin "2") (pinfunction "2_2") (pintype "passive"))
      (node (ref "C46") (pin "2") (pinfunction "2_2") (pintype "passive"))
      (node (ref "C47") (pin "2") (pinfunction "2_2") (pintype "passive"))
      (node (ref "C48") (pin "2") (pinfunction "2_2") (pintype "passive"))
      (node (ref "C49") (pin "2") (pinfunction "2_2") (pintype "passive"))
      (node (ref "C5") (pin "2") (pinfunction "2_2") (pintype "passive"))
      (node (ref "C50") (pin "2") (pinfunction "2_2") (pintype "passive"))
      (node (ref "C51") (pin "2") (pinfunction "2_2") (pintype "passive"))
      (node (ref "C52") (pin "2") (pinfunction "2_2") (pintype "passive"))
      (node (ref "C53") (pin "2") (pinfunction "2_2") (pintype "passive"))
      (node (ref "C54") (pin "2") (pinfunction "2_2") (pintype "passive"))
      (node (ref "C55") (pin "2") (pinfunction "2_2") (pintype "passive"))
      (node (ref "C56") (pin "2") (pinfunction "2_2") (pintype "passive"))
      (node (ref "C57") (pin "2") (pinfunction "2_2") (pintype "passive"))
      (node (ref "C58") (pin "2") (pinfunction "2_2") (pintype "passive"))
      (node (ref "C59") (pin "2") (pinfunction "2_2") (pintype "passive"))
      (node (ref "C6") (pin "2") (pinfunction "2_2") (pintype "passive"))
      (node (ref "C60") (pin "2") (pinfunction "2_2") (pintype "passive"))
      (node (ref "C61") (pin "2") (pinfunction "2_2") (pintype "passive"))
      (node (ref "C62") (pin "2") (pinfunction "2_2") (pintype "passive"))
      (node (ref "C63") (pin "2") (pinfunction "2_2") (pintype "passive"))
      (node (ref "C64") (pin "2") (pinfunction "2_2") (pintype "passive"))
      (node (ref "C65") (pin "2") (pinfunction "2_2") (pintype "passive"))
      (node (ref "C66") (pin "2") (pinfunction "2_2") (pintype "passive"))
      (node (ref "C67") (pin "2") (pinfunction "2_2") (pintype "passive"))
      (node (ref "C68") (pin "2") (pinfunction "2_2") (pintype "passive"))
      (node (ref "C69") (pin "2") (pinfunction "2_2") (pintype "passive"))
      (node (ref "C7") (pin "2") (pinfunction "2_2") (pintype "passive"))
      (node (ref "C70") (pin "2") (pinfunction "2_2") (pintype "passive"))
      (node (ref "C71") (pin "2") (pinfunction "2_2") (pintype "passive"))
      (node (ref "C72") (pin "2") (pinfunction "2_2") (pintype "passive"))
      (node (ref "C73") (pin "2") (pinfunction "2_2") (pintype "passive"))
      (node (ref "C74") (pin "2") (pinfunction "2_2") (pintype "passive"))
      (node (ref "C75") (pin "2") (pinfunction "2_2") (pintype "passive"))
      (node (ref "C76") (pin "2") (pinfunction "2_2") (pintype "passive"))
      (node (ref "C77") (pin "2") (pinfunction "2_2") (pintype "passive"))
      (node (ref "C78") (pin "2") (pinfunction "2_2") (pintype "passive"))
      (node (ref "C79") (pin "2") (pinfunction "2_2") (pintype "passive"))
      (node (ref "C8") (pin "2") (pinfunction "2_2") (pintype "passive"))
      (node (ref "C80") (pin "2") (pinfunction "2_2") (pintype "passive"))
      (node (ref "C81") (pin "2") (pinfunction "2_2") (pintype "passive"))
      (node (ref "C82") (pin "2") (pinfunction "2_2") (pintype "passive"))
      (node (ref "C83") (pin "2") (pinfunction "2_2") (pintype "passive"))
      (node (ref "C84") (pin "2") (pinfunction "2_2") (pintype "passive"))
      (node (ref "C85") (pin "2") (pinfunction "2_2") (pintype "passive"))
      (node (ref "C86") (pin "2") (pinfunction "2_2") (pintype "passive"))
      (node (ref "C87") (pin "2") (pinfunction "2_2") (pintype "passive"))
      (node (ref "C88") (pin "2") (pinfunction "2_2") (pintype "passive"))
      (node (ref "C89") (pin "2") (pinfunction "2_2") (pintype "passive"))
      (node (ref "C9") (pin "2") (pinfunction "2_2") (pintype "passive"))
      (node (ref "C90") (pin "2") (pinfunction "2_2") (pintype "passive"))
      (node (ref "C91") (pin "1") (pinfunction "1_1") (pintype "passive"))
      (node (ref "C92") (pin "2") (pinfunction "2_2") (pintype "passive"))
      (node (ref "C93") (pin "2") (pinfunction "2_2") (pintype "passive"))
      (node (ref "GND") (pin "TP") (pinfunction "TP_TP") (pintype "input"))
      (node (ref "GND75") (pin "TP") (pinfunction "TP_TP") (pintype "input"))
      (node (ref "GND77") (pin "TP") (pinfunction "TP_TP") (pintype "input"))
      (node (ref "R12") (pin "2") (pinfunction "2_2") (pintype "passive"))
      (node (ref "R15") (pin "2") (pinfunction "2_2") (pintype "passive"))
      (node (ref "R18") (pin "2") (pinfunction "2_2") (pintype "passive"))
      (node (ref "R22") (pin "1") (pinfunction "1_1") (pintype "passive"))
      (node (ref "R2X") (pin "2") (pinfunction "2_2") (pintype "passive"))
      (node (ref "R3") (pin "2") (pinfunction "2_2") (pintype "passive"))
      (node (ref "R6") (pin "2") (pinfunction "2_2") (pintype "passive"))
      (node (ref "R9") (pin "2") (pinfunction "2_2") (pintype "passive"))
      (node (ref "SENSOR") (pin "A21") (pinfunction "GND_A21") (pintype "power_in"))
      (node (ref "SENSOR") (pin "A25") (pinfunction "GND_A25") (pintype "power_in"))
      (node (ref "SENSOR") (pin "A28") (pinfunction "GND_A28") (pintype "power_in"))
      (node (ref "SENSOR") (pin "A29") (pinfunction "GND_A29") (pintype "power_in"))
      (node (ref "SENSOR") (pin "A9") (pinfunction "GND_A9") (pintype "power_in"))
      (node (ref "SENSOR") (pin "B22") (pinfunction "GND_B22") (pintype "power_in"))
      (node (ref "SENSOR") (pin "B26") (pinfunction "GND_B26") (pintype "power_in"))
      (node (ref "SENSOR") (pin "B27") (pinfunction "GND_B27") (pintype "power_in"))
      (node (ref "SENSOR") (pin "B28") (pinfunction "GND_B28") (pintype "power_in"))
      (node (ref "SENSOR") (pin "B5") (pinfunction "GND_B5") (pintype "power_in"))
      (node (ref "SENSOR") (pin "C15") (pinfunction "GND_C15") (pintype "power_in"))
      (node (ref "SENSOR") (pin "C16") (pinfunction "GND_C16") (pintype "power_in"))
      (node (ref "SENSOR") (pin "C28") (pinfunction "GND_C28") (pintype "power_in"))
      (node (ref "SENSOR") (pin "D2") (pinfunction "GND_D2") (pintype "power_in"))
      (node (ref "SENSOR") (pin "D25") (pinfunction "GND_D25") (pintype "power_in"))
      (node (ref "SENSOR") (pin "D27") (pinfunction "GND_D27") (pintype "power_in"))
      (node (ref "SENSOR") (pin "D29") (pinfunction "GND_D29") (pintype "power_in"))
      (node (ref "SENSOR") (pin "E15") (pinfunction "GND_E15") (pintype "power_in"))
      (node (ref "SENSOR") (pin "E16") (pinfunction "GND_E16") (pintype "power_in"))
      (node (ref "SENSOR") (pin "E25") (pinfunction "GND_E25") (pintype "power_in"))
      (node (ref "SENSOR") (pin "E27") (pinfunction "GND_E27") (pintype "power_in"))
      (node (ref "SENSOR") (pin "E3") (pinfunction "GND_E3") (pintype "power_in"))
      (node (ref "SENSOR") (pin "E4") (pinfunction "DIO2_E4") (pintype "output"))
      (node (ref "SENSOR") (pin "F27") (pinfunction "GND_F27") (pintype "power_in"))
      (node (ref "SENSOR") (pin "F4") (pinfunction "DIO1_F4") (pintype "output"))
      (node (ref "SENSOR") (pin "G3") (pinfunction "DIO4_G3") (pintype "output"))
      (node (ref "SENSOR") (pin "G5") (pinfunction "GND_G5") (pintype "power_in"))
      (node (ref "SENSOR") (pin "H1") (pinfunction "GND_H1") (pintype "power_in"))
      (node (ref "SENSOR") (pin "H21") (pinfunction "GND_H21") (pintype "power_in"))
      (node (ref "SENSOR") (pin "H25") (pinfunction "GND_H25") (pintype "power_in"))
      (node (ref "SENSOR") (pin "H27") (pinfunction "GND_H27") (pintype "power_in"))
      (node (ref "SENSOR") (pin "H4") (pinfunction "DIO3_H4") (pintype "output"))
      (node (ref "SENSOR") (pin "H6") (pinfunction "GND_H6") (pintype "power_in"))
      (node (ref "SENSOR") (pin "H9") (pinfunction "GND_H9") (pintype "power_in"))
      (node (ref "U1") (pin "6") (pinfunction "ANODE_6") (pintype "input"))
      (node (ref "U2") (pin "6") (pinfunction "ANODE_6") (pintype "input"))
      (node (ref "U3") (pin "2") (pinfunction "GND_2") (pintype "power_in"))
      (node (ref "U3") (pin "EP") (pinfunction "EP_EP") (pintype "power_in"))
      (node (ref "U4") (pin "16") (pinfunction "DIR2_16") (pintype "input"))
      (node (ref "U4") (pin "7") (pinfunction "~{OE}_7") (pintype "input"))
      (node (ref "U4") (pin "8") (pinfunction "GND_8") (pintype "passive"))
      (node (ref "U5") (pin "6") (pinfunction "DIR4_6") (pintype "input"))
      (node (ref "U5") (pin "7") (pinfunction "~{OE}_7") (pintype "input"))
      (node (ref "U5") (pin "8") (pinfunction "GND_8") (pintype "passive"))
      (node (ref "U6") (pin "16") (pinfunction "DIR2_16") (pintype "input"))
      (node (ref "U6") (pin "7") (pinfunction "~{OE}_7") (pintype "input"))
      (node (ref "U6") (pin "8") (pinfunction "GND_8") (pintype "passive"))
      (node (ref "U7") (pin "4") (pinfunction "GND_4") (pintype "power_in"))
      (node (ref "U7") (pin "5") (pinfunction "A2_5") (pintype "input"))
      (node (ref "U7") (pin "6") (pinfunction "A1_6") (pintype "input"))
      (node (ref "U7") (pin "7") (pinfunction "A0_7") (pintype "input"))
      (node (ref "UEP") (pin "1") (pinfunction "A0_1") (pintype "input"))
      (node (ref "UEP") (pin "2") (pinfunction "A1_2") (pintype "input"))
      (node (ref "UEP") (pin "3") (pinfunction "A2_3") (pintype "input"))
      (node (ref "UEP") (pin "4") (pinfunction "GND_4") (pintype "passive"))
      (node (ref "UEP") (pin "EP") (pinfunction "EP_EP") (pintype "passive"))
      (node (ref "UNE") (pin "4") (pinfunction "VSS_4") (pintype "power_in"))
      (node (ref "UNE") (pin "EP") (pinfunction "EP_EP") (pintype "passive"))
      (node (ref "UNN") (pin "4") (pinfunction "VSS_4") (pintype "power_in"))
      (node (ref "UNN") (pin "EP") (pinfunction "EP_EP") (pintype "passive"))
      (node (ref "UNW") (pin "4") (pinfunction "VSS_4") (pintype "power_in"))
      (node (ref "UNW") (pin "EP") (pinfunction "EP_EP") (pintype "passive"))
      (node (ref "USE") (pin "4") (pinfunction "VSS_4") (pintype "power_in"))
      (node (ref "USE") (pin "EP") (pinfunction "EP_EP") (pintype "passive"))
      (node (ref "USS") (pin "4") (pinfunction "VSS_4") (pintype "power_in"))
      (node (ref "USS") (pin "EP") (pinfunction "EP_EP") (pintype "passive"))
      (node (ref "USW") (pin "4") (pinfunction "VSS_4") (pintype "power_in"))
      (node (ref "USW") (pin "EP") (pinfunction "EP_EP") (pintype "passive"))
      (node (ref "X-NORTH") (pin "102") (pinfunction "102_102") (pintype "bidirectional"))
      (node (ref "X-NORTH") (pin "103") (pinfunction "103_103") (pintype "bidirectional"))
      (node (ref "X-NORTH") (pin "108") (pinfunction "108_108") (pintype "bidirectional"))
      (node (ref "X-NORTH") (pin "114") (pinfunction "114_114") (pintype "bidirectional"))
      (node (ref "X-NORTH") (pin "12") (pinfunction "12_12") (pintype "bidirectional"))
      (node (ref "X-NORTH") (pin "120") (pinfunction "120_120") (pintype "bidirectional"))
      (node (ref "X-NORTH") (pin "126") (pinfunction "126_126") (pintype "bidirectional"))
      (node (ref "X-NORTH") (pin "132") (pinfunction "132_132") (pintype "bidirectional"))
      (node (ref "X-NORTH") (pin "138") (pinfunction "138_138") (pintype "bidirectional"))
      (node (ref "X-NORTH") (pin "139") (pinfunction "139_139") (pintype "bidirectional"))
      (node (ref "X-NORTH") (pin "18") (pinfunction "18_18") (pintype "bidirectional"))
      (node (ref "X-NORTH") (pin "24") (pinfunction "24_24") (pintype "bidirectional"))
      (node (ref "X-NORTH") (pin "30") (pinfunction "30_30") (pintype "bidirectional"))
      (node (ref "X-NORTH") (pin "36") (pinfunction "36_36") (pintype "bidirectional"))
      (node (ref "X-NORTH") (pin "42") (pinfunction "42_42") (pintype "bidirectional"))
      (node (ref "X-NORTH") (pin "43") (pinfunction "43_43") (pintype "bidirectional"))
      (node (ref "X-NORTH") (pin "48") (pinfunction "48_48") (pintype "bidirectional"))
      (node (ref "X-NORTH") (pin "54") (pinfunction "54_54") (pintype "bidirectional"))
      (node (ref "X-NORTH") (pin "60") (pinfunction "60_60") (pintype "bidirectional"))
      (node (ref "X-NORTH") (pin "66") (pinfunction "66_66") (pintype "bidirectional"))
      (node (ref "X-NORTH") (pin "72") (pinfunction "72_72") (pintype "bidirectional"))
      (node (ref "X-NORTH") (pin "78") (pinfunction "78_78") (pintype "bidirectional"))
      (node (ref "X-NORTH") (pin "84") (pinfunction "84_84") (pintype "bidirectional"))
      (node (ref "X-NORTH") (pin "90") (pinfunction "90_90") (pintype "bidirectional"))
      (node (ref "X-NORTH") (pin "96") (pinfunction "96_96") (pintype "bidirectional"))
      (node (ref "X-SOUTH") (pin "102") (pinfunction "102_102") (pintype "bidirectional"))
      (node (ref "X-SOUTH") (pin "103") (pinfunction "103_103") (pintype "bidirectional"))
      (node (ref "X-SOUTH") (pin "108") (pinfunction "108_108") (pintype "bidirectional"))
      (node (ref "X-SOUTH") (pin "114") (pinfunction "114_114") (pintype "bidirectional"))
      (node (ref "X-SOUTH") (pin "12") (pinfunction "12_12") (pintype "bidirectional"))
      (node (ref "X-SOUTH") (pin "120") (pinfunction "120_120") (pintype "bidirectional"))
      (node (ref "X-SOUTH") (pin "126") (pinfunction "126_126") (pintype "bidirectional"))
      (node (ref "X-SOUTH") (pin "132") (pinfunction "132_132") (pintype "bidirectional"))
      (node (ref "X-SOUTH") (pin "138") (pinfunction "138_138") (pintype "bidirectional"))
      (node (ref "X-SOUTH") (pin "139") (pinfunction "139_139") (pintype "bidirectional"))
      (node (ref "X-SOUTH") (pin "18") (pinfunction "18_18") (pintype "bidirectional"))
      (node (ref "X-SOUTH") (pin "24") (pinfunction "24_24") (pintype "bidirectional"))
      (node (ref "X-SOUTH") (pin "30") (pinfunction "30_30") (pintype "bidirectional"))
      (node (ref "X-SOUTH") (pin "36") (pinfunction "36_36") (pintype "bidirectional"))
      (node (ref "X-SOUTH") (pin "42") (pinfunction "42_42") (pintype "bidirectional"))
      (node (ref "X-SOUTH") (pin "43") (pinfunction "43_43") (pintype "bidirectional"))
      (node (ref "X-SOUTH") (pin "48") (pinfunction "48_48") (pintype "bidirectional"))
      (node (ref "X-SOUTH") (pin "54") (pinfunction "54_54") (pintype "bidirectional"))
      (node (ref "X-SOUTH") (pin "60") (pinfunction "60_60") (pintype "bidirectional"))
      (node (ref "X-SOUTH") (pin "66") (pinfunction "66_66") (pintype "bidirectional"))
      (node (ref "X-SOUTH") (pin "72") (pinfunction "72_72") (pintype "bidirectional"))
      (node (ref "X-SOUTH") (pin "78") (pinfunction "78_78") (pintype "bidirectional"))
      (node (ref "X-SOUTH") (pin "84") (pinfunction "84_84") (pintype "bidirectional"))
      (node (ref "X-SOUTH") (pin "90") (pinfunction "90_90") (pintype "bidirectional"))
      (node (ref "X-SOUTH") (pin "96") (pinfunction "96_96") (pintype "bidirectional"))
    )
    (net (code "4") (name "N$42") (class "Default")
      (node (ref "SENSOR") (pin "A2") (pinfunction "TANA_A2") (pintype "output"))
    )
    (net (code "5") (name "N00_N") (class "Default")
      (node (ref "R25") (pin "2") (pinfunction "2_2") (pintype "passive"))
      (node (ref "SENSOR") (pin "E6") (pinfunction "LVDS_CLK_P_E6") (pintype "input"))
      (node (ref "X-NORTH") (pin "16") (pinfunction "16_16") (pintype "bidirectional"))
    )
    (net (code "6") (name "N00_P") (class "Default")
      (node (ref "R25") (pin "1") (pinfunction "1_1") (pintype "passive"))
      (node (ref "SENSOR") (pin "E5") (pinfunction "LVDS_CLK_N_E5") (pintype "input"))
      (node (ref "X-NORTH") (pin "14") (pinfunction "14_14") (pintype "bidirectional"))
    )
    (net (code "7") (name "N01_N") (class "Default")
      (node (ref "SENSOR") (pin "G7") (pinfunction "OUTCLK_P_G7") (pintype "output"))
      (node (ref "X-NORTH") (pin "17") (pinfunction "17_17") (pintype "bidirectional"))
    )
    (net (code "8") (name "N01_P") (class "Default")
      (node (ref "SENSOR") (pin "G6") (pinfunction "OUTCLK_N_G6") (pintype "output"))
      (node (ref "X-NORTH") (pin "15") (pinfunction "15_15") (pintype "bidirectional"))
    )
    (net (code "9") (name "N02_N") (class "Default")
      (node (ref "SENSOR") (pin "F7") (pinfunction "OUT33_P_F7") (pintype "output"))
      (node (ref "X-NORTH") (pin "22") (pinfunction "22_22") (pintype "bidirectional"))
    )
    (net (code "10") (name "N02_P") (class "Default")
      (node (ref "SENSOR") (pin "F6") (pinfunction "OUT33_N_F6") (pintype "output"))
      (node (ref "X-NORTH") (pin "20") (pinfunction "20_20") (pintype "bidirectional"))
    )
    (net (code "11") (name "N03_N") (class "Default")
      (node (ref "X-NORTH") (pin "23") (pinfunction "23_23") (pintype "bidirectional"))
    )
    (net (code "12") (name "N03_P") (class "Default")
      (node (ref "X-NORTH") (pin "21") (pinfunction "21_21") (pintype "bidirectional"))
    )
    (net (code "13") (name "N04_N") (class "Default")
      (node (ref "SENSOR") (pin "E8") (pinfunction "OUT35_P_E8") (pintype "output"))
      (node (ref "X-NORTH") (pin "28") (pinfunction "28_28") (pintype "bidirectional"))
    )
    (net (code "14") (name "N04_P") (class "Default")
      (node (ref "SENSOR") (pin "E7") (pinfunction "OUT35_N_E7") (pintype "output"))
      (node (ref "X-NORTH") (pin "26") (pinfunction "26_26") (pintype "bidirectional"))
    )
    (net (code "15") (name "N05_N") (class "Default")
      (node (ref "SENSOR") (pin "H8") (pinfunction "OUT34_P_H8") (pintype "output"))
      (node (ref "X-NORTH") (pin "29") (pinfunction "29_29") (pintype "bidirectional"))
    )
    (net (code "16") (name "N05_P") (class "Default")
      (node (ref "SENSOR") (pin "H7") (pinfunction "OUT34_N_H7") (pintype "output"))
      (node (ref "X-NORTH") (pin "27") (pinfunction "27_27") (pintype "bidirectional"))
    )
    (net (code "17") (name "N06_N") (class "Default")
      (node (ref "SENSOR") (pin "F9") (pinfunction "OUT37_P_F9") (pintype "output"))
      (node (ref "X-NORTH") (pin "34") (pinfunction "34_34") (pintype "bidirectional"))
    )
    (net (code "18") (name "N06_P") (class "Default")
      (node (ref "SENSOR") (pin "F8") (pinfunction "OUT37_N_F8") (pintype "output"))
      (node (ref "X-NORTH") (pin "32") (pinfunction "32_32") (pintype "bidirectional"))
    )
    (net (code "19") (name "N07_N") (class "Default")
      (node (ref "SENSOR") (pin "G9") (pinfunction "OUT36_P_G9") (pintype "output"))
      (node (ref "X-NORTH") (pin "35") (pinfunction "35_35") (pintype "bidirectional"))
    )
    (net (code "20") (name "N07_P") (class "Default")
      (node (ref "SENSOR") (pin "G8") (pinfunction "OUT36_N_G8") (pintype "output"))
      (node (ref "X-NORTH") (pin "33") (pinfunction "33_33") (pintype "bidirectional"))
    )
    (net (code "21") (name "N08_N") (class "Default")
      (node (ref "SENSOR") (pin "E10") (pinfunction "OUT38_P_E10") (pintype "output"))
      (node (ref "X-NORTH") (pin "40") (pinfunction "40_40") (pintype "bidirectional"))
    )
    (net (code "22") (name "N08_P") (class "Default")
      (node (ref "SENSOR") (pin "E9") (pinfunction "OUT38_N_E9") (pintype "output"))
      (node (ref "X-NORTH") (pin "38") (pinfunction "38_38") (pintype "bidirectional"))
    )
    (net (code "23") (name "N09_N") (class "Default")
      (node (ref "SENSOR") (pin "G11") (pinfunction "OUT39_P_G11") (pintype "output"))
      (node (ref "X-NORTH") (pin "41") (pinfunction "41_41") (pintype "bidirectional"))
    )
    (net (code "24") (name "N09_P") (class "Default")
      (node (ref "SENSOR") (pin "G10") (pinfunction "OUT39_N_G10") (pintype "output"))
      (node (ref "X-NORTH") (pin "39") (pinfunction "39_39") (pintype "bidirectional"))
    )
    (net (code "25") (name "N10_N") (class "Default")
      (node (ref "SENSOR") (pin "F11") (pinfunction "OUT40_P_F11") (pintype "output"))
      (node (ref "X-NORTH") (pin "46") (pinfunction "46_46") (pintype "bidirectional"))
    )
    (net (code "26") (name "N10_P") (class "Default")
      (node (ref "SENSOR") (pin "F10") (pinfunction "OUT40_N_F10") (pintype "output"))
      (node (ref "X-NORTH") (pin "44") (pinfunction "44_44") (pintype "bidirectional"))
    )
    (net (code "27") (name "N11_N") (class "Default")
      (node (ref "SENSOR") (pin "H12") (pinfunction "OUT41_P_H12") (pintype "output"))
      (node (ref "X-NORTH") (pin "47") (pinfunction "47_47") (pintype "bidirectional"))
    )
    (net (code "28") (name "N11_P") (class "Default")
      (node (ref "SENSOR") (pin "H11") (pinfunction "OUT41_N_H11") (pintype "output"))
      (node (ref "X-NORTH") (pin "45") (pinfunction "45_45") (pintype "bidirectional"))
    )
    (net (code "29") (name "N12_N") (class "Default")
      (node (ref "SENSOR") (pin "E12") (pinfunction "OUT42_P_E12") (pintype "output"))
      (node (ref "X-NORTH") (pin "52") (pinfunction "52_52") (pintype "bidirectional"))
    )
    (net (code "30") (name "N12_P") (class "Default")
      (node (ref "SENSOR") (pin "E11") (pinfunction "OUT42_N_E11") (pintype "output"))
      (node (ref "X-NORTH") (pin "50") (pinfunction "50_50") (pintype "bidirectional"))
    )
    (net (code "31") (name "N13_N") (class "Default")
      (node (ref "SENSOR") (pin "G13") (pinfunction "OUT43_P_G13") (pintype "output"))
      (node (ref "X-NORTH") (pin "53") (pinfunction "53_53") (pintype "bidirectional"))
    )
    (net (code "32") (name "N13_P") (class "Default")
      (node (ref "SENSOR") (pin "G12") (pinfunction "OUT43_N_G12") (pintype "output"))
      (node (ref "X-NORTH") (pin "51") (pinfunction "51_51") (pintype "bidirectional"))
    )
    (net (code "33") (name "N14_N") (class "Default")
      (node (ref "SENSOR") (pin "F13") (pinfunction "OUT44_P_F13") (pintype "output"))
      (node (ref "X-NORTH") (pin "58") (pinfunction "58_58") (pintype "bidirectional"))
    )
    (net (code "34") (name "N14_P") (class "Default")
      (node (ref "SENSOR") (pin "F12") (pinfunction "OUT44_N_F12") (pintype "output"))
      (node (ref "X-NORTH") (pin "56") (pinfunction "56_56") (pintype "bidirectional"))
    )
    (net (code "35") (name "N15_N") (class "Default")
      (node (ref "SENSOR") (pin "H14") (pinfunction "OUT45_P_H14") (pintype "output"))
      (node (ref "X-NORTH") (pin "59") (pinfunction "59_59") (pintype "bidirectional"))
    )
    (net (code "36") (name "N15_P") (class "Default")
      (node (ref "SENSOR") (pin "H13") (pinfunction "OUT45_N_H13") (pintype "output"))
      (node (ref "X-NORTH") (pin "57") (pinfunction "57_57") (pintype "bidirectional"))
    )
    (net (code "37") (name "N16_N") (class "Default")
      (node (ref "SENSOR") (pin "E14") (pinfunction "OUT46_P_E14") (pintype "output"))
      (node (ref "X-NORTH") (pin "64") (pinfunction "64_64") (pintype "bidirectional"))
    )
    (net (code "38") (name "N16_P") (class "Default")
      (node (ref "SENSOR") (pin "E13") (pinfunction "OUT46_N_E13") (pintype "output"))
      (node (ref "X-NORTH") (pin "62") (pinfunction "62_62") (pintype "bidirectional"))
    )
    (net (code "39") (name "N17_N") (class "Default")
      (node (ref "SENSOR") (pin "G15") (pinfunction "OUT47_P_G15") (pintype "output"))
      (node (ref "X-NORTH") (pin "65") (pinfunction "65_65") (pintype "bidirectional"))
    )
    (net (code "40") (name "N17_P") (class "Default")
      (node (ref "SENSOR") (pin "G14") (pinfunction "OUT47_N_G14") (pintype "output"))
      (node (ref "X-NORTH") (pin "63") (pinfunction "63_63") (pintype "bidirectional"))
    )
    (net (code "41") (name "N18_N") (class "Default")
      (node (ref "SENSOR") (pin "F15") (pinfunction "OUT48_P_F15") (pintype "output"))
      (node (ref "X-NORTH") (pin "70") (pinfunction "70_70") (pintype "bidirectional"))
    )
    (net (code "42") (name "N18_P") (class "Default")
      (node (ref "SENSOR") (pin "F14") (pinfunction "OUT48_N_F14") (pintype "output"))
      (node (ref "X-NORTH") (pin "68") (pinfunction "68_68") (pintype "bidirectional"))
    )
    (net (code "43") (name "N19_N") (class "Default")
      (node (ref "SENSOR") (pin "G17") (pinfunction "OUT50_P_G17") (pintype "output"))
      (node (ref "X-NORTH") (pin "71") (pinfunction "71_71") (pintype "bidirectional"))
    )
    (net (code "44") (name "N19_P") (class "Default")
      (node (ref "SENSOR") (pin "G16") (pinfunction "OUT50_N_G16") (pintype "output"))
      (node (ref "X-NORTH") (pin "69") (pinfunction "69_69") (pintype "bidirectional"))
    )
    (net (code "45") (name "N20_N") (class "Default")
      (node (ref "SENSOR") (pin "F17") (pinfunction "OUT49_P_F17") (pintype "output"))
      (node (ref "X-NORTH") (pin "76") (pinfunction "76_76") (pintype "bidirectional"))
    )
    (net (code "46") (name "N20_P") (class "Default")
      (node (ref "SENSOR") (pin "F16") (pinfunction "OUT49_N_F16") (pintype "output"))
      (node (ref "X-NORTH") (pin "74") (pinfunction "74_74") (pintype "bidirectional"))
    )
    (net (code "47") (name "N21_N") (class "Default")
      (node (ref "SENSOR") (pin "H18") (pinfunction "OUT52_P_H18") (pintype "output"))
      (node (ref "X-NORTH") (pin "77") (pinfunction "77_77") (pintype "bidirectional"))
    )
    (net (code "48") (name "N21_P") (class "Default")
      (node (ref "SENSOR") (pin "H17") (pinfunction "OUT52_N_H17") (pintype "output"))
      (node (ref "X-NORTH") (pin "75") (pinfunction "75_75") (pintype "bidirectional"))
    )
    (net (code "49") (name "N22_N") (class "Default")
      (node (ref "SENSOR") (pin "E18") (pinfunction "OUT51_P_E18") (pintype "output"))
      (node (ref "X-NORTH") (pin "82") (pinfunction "82_82") (pintype "bidirectional"))
    )
    (net (code "50") (name "N22_P") (class "Default")
      (node (ref "SENSOR") (pin "E17") (pinfunction "OUT51_N_E17") (pintype "output"))
      (node (ref "X-NORTH") (pin "80") (pinfunction "80_80") (pintype "bidirectional"))
    )
    (net (code "51") (name "N23_N") (class "Default")
      (node (ref "SENSOR") (pin "G19") (pinfunction "OUT54_P_G19") (pintype "output"))
      (node (ref "X-NORTH") (pin "83") (pinfunction "83_83") (pintype "bidirectional"))
    )
    (net (code "52") (name "N23_P") (class "Default")
      (node (ref "SENSOR") (pin "G18") (pinfunction "OUT54_N_G18") (pintype "output"))
      (node (ref "X-NORTH") (pin "81") (pinfunction "81_81") (pintype "bidirectional"))
    )
    (net (code "53") (name "N24_N") (class "Default")
      (node (ref "SENSOR") (pin "F19") (pinfunction "OUT53_P_F19") (pintype "output"))
      (node (ref "X-NORTH") (pin "88") (pinfunction "88_88") (pintype "bidirectional"))
    )
    (net (code "54") (name "N24_P") (class "Default")
      (node (ref "SENSOR") (pin "F18") (pinfunction "OUT53_N_F18") (pintype "output"))
      (node (ref "X-NORTH") (pin "86") (pinfunction "86_86") (pintype "bidirectional"))
    )
    (net (code "55") (name "N25_N") (class "Default")
      (node (ref "SENSOR") (pin "H20") (pinfunction "OUT56_P_H20") (pintype "output"))
      (node (ref "X-NORTH") (pin "89") (pinfunction "89_89") (pintype "bidirectional"))
    )
    (net (code "56") (name "N25_P") (class "Default")
      (node (ref "SENSOR") (pin "H19") (pinfunction "OUT56_N_H19") (pintype "output"))
      (node (ref "X-NORTH") (pin "87") (pinfunction "87_87") (pintype "bidirectional"))
    )
    (net (code "57") (name "N26_N") (class "Default")
      (node (ref "SENSOR") (pin "E20") (pinfunction "OUT55_P_E20") (pintype "output"))
      (node (ref "X-NORTH") (pin "94") (pinfunction "94_94") (pintype "bidirectional"))
    )
    (net (code "58") (name "N26_P") (class "Default")
      (node (ref "SENSOR") (pin "E19") (pinfunction "OUT55_N_E19") (pintype "output"))
      (node (ref "X-NORTH") (pin "92") (pinfunction "92_92") (pintype "bidirectional"))
    )
    (net (code "59") (name "N27_N") (class "Default")
      (node (ref "SENSOR") (pin "G21") (pinfunction "OUT58_P_G21") (pintype "output"))
      (node (ref "X-NORTH") (pin "95") (pinfunction "95_95") (pintype "bidirectional"))
    )
    (net (code "60") (name "N27_P") (class "Default")
      (node (ref "SENSOR") (pin "G20") (pinfunction "OUT58_N_G20") (pintype "output"))
      (node (ref "X-NORTH") (pin "93") (pinfunction "93_93") (pintype "bidirectional"))
    )
    (net (code "61") (name "N28_N") (class "Default")
      (node (ref "SENSOR") (pin "F21") (pinfunction "OUT57_P_F21") (pintype "output"))
      (node (ref "X-NORTH") (pin "100") (pinfunction "100_100") (pintype "bidirectional"))
    )
    (net (code "62") (name "N28_P") (class "Default")
      (node (ref "SENSOR") (pin "F20") (pinfunction "OUT57_N_F20") (pintype "output"))
      (node (ref "X-NORTH") (pin "98") (pinfunction "98_98") (pintype "bidirectional"))
    )
    (net (code "63") (name "N29_N") (class "Default")
      (node (ref "SENSOR") (pin "G23") (pinfunction "OUT61_P_G23") (pintype "output"))
      (node (ref "X-NORTH") (pin "101") (pinfunction "101_101") (pintype "bidirectional"))
    )
    (net (code "64") (name "N29_P") (class "Default")
      (node (ref "SENSOR") (pin "G22") (pinfunction "OUT61_N_G22") (pintype "output"))
      (node (ref "X-NORTH") (pin "99") (pinfunction "99_99") (pintype "bidirectional"))
    )
    (net (code "65") (name "N30_N") (class "Default")
      (node (ref "SENSOR") (pin "E22") (pinfunction "OUT59_P_E22") (pintype "output"))
      (node (ref "X-NORTH") (pin "106") (pinfunction "106_106") (pintype "bidirectional"))
    )
    (net (code "66") (name "N30_P") (class "Default")
      (node (ref "SENSOR") (pin "E21") (pinfunction "OUT59_N_E21") (pintype "output"))
      (node (ref "X-NORTH") (pin "104") (pinfunction "104_104") (pintype "bidirectional"))
    )
    (net (code "67") (name "N31_N") (class "Default")
      (node (ref "SENSOR") (pin "H24") (pinfunction "OUT63_P_H24") (pintype "output"))
      (node (ref "X-NORTH") (pin "107") (pinfunction "107_107") (pintype "bidirectional"))
    )
    (net (code "68") (name "N31_P") (class "Default")
      (node (ref "SENSOR") (pin "H23") (pinfunction "OUT63_N_H23") (pintype "output"))
      (node (ref "X-NORTH") (pin "105") (pinfunction "105_105") (pintype "bidirectional"))
    )
    (net (code "69") (name "N32_N") (class "Default")
      (node (ref "SENSOR") (pin "F23") (pinfunction "OUT60_P_F23") (pintype "output"))
      (node (ref "X-NORTH") (pin "112") (pinfunction "112_112") (pintype "bidirectional"))
    )
    (net (code "70") (name "N32_P") (class "Default")
      (node (ref "SENSOR") (pin "F22") (pinfunction "OUT60_N_F22") (pintype "output"))
      (node (ref "X-NORTH") (pin "110") (pinfunction "110_110") (pintype "bidirectional"))
    )
    (net (code "71") (name "N33_N") (class "Default")
      (node (ref "SENSOR") (pin "G25") (pinfunction "OUT64_P_G25") (pintype "output"))
      (node (ref "X-NORTH") (pin "113") (pinfunction "113_113") (pintype "bidirectional"))
    )
    (net (code "72") (name "N33_P") (class "Default")
      (node (ref "SENSOR") (pin "G24") (pinfunction "OUT64_N_G24") (pintype "output"))
      (node (ref "X-NORTH") (pin "111") (pinfunction "111_111") (pintype "bidirectional"))
    )
    (net (code "73") (name "N34_N") (class "Default")
      (node (ref "SENSOR") (pin "E24") (pinfunction "OUT62_P_E24") (pintype "output"))
      (node (ref "X-NORTH") (pin "118") (pinfunction "118_118") (pintype "bidirectional"))
    )
    (net (code "74") (name "N34_P") (class "Default")
      (node (ref "SENSOR") (pin "E23") (pinfunction "OUT62_N_E23") (pintype "output"))
      (node (ref "X-NORTH") (pin "116") (pinfunction "116_116") (pintype "bidirectional"))
    )
    (net (code "75") (name "N35_N") (class "Default")
      (node (ref "U6") (pin "4") (pinfunction "A4_4") (pintype "bidirectional"))
      (node (ref "X-NORTH") (pin "119") (pinfunction "119_119") (pintype "bidirectional"))
    )
    (net (code "76") (name "N35_P") (class "Default")
      (node (ref "U6") (pin "3") (pinfunction "A3_3") (pintype "bidirectional"))
      (node (ref "X-NORTH") (pin "117") (pinfunction "117_117") (pintype "bidirectional"))
    )
    (net (code "77") (name "N36_N") (class "Default")
      (node (ref "X-NORTH") (pin "124") (pinfunction "124_124") (pintype "bidirectional"))
    )
    (net (code "78") (name "N36_P") (class "Default")
      (node (ref "X-NORTH") (pin "122") (pinfunction "122_122") (pintype "bidirectional"))
    )
    (net (code "79") (name "N37_N") (class "Default")
      (node (ref "U5") (pin "3") (pinfunction "A3_3") (pintype "bidirectional"))
      (node (ref "X-NORTH") (pin "125") (pinfunction "125_125") (pintype "bidirectional"))
    )
    (net (code "80") (name "N37_P") (class "Default")
      (node (ref "U5") (pin "4") (pinfunction "A4_4") (pintype "bidirectional"))
      (node (ref "X-NORTH") (pin "123") (pinfunction "123_123") (pintype "bidirectional"))
    )
    (net (code "81") (name "N38_N") (class "Default")
      (node (ref "U6") (pin "2") (pinfunction "A2_2") (pintype "bidirectional"))
      (node (ref "X-NORTH") (pin "130") (pinfunction "130_130") (pintype "bidirectional"))
    )
    (net (code "82") (name "N38_P") (class "Default")
      (node (ref "U6") (pin "1") (pinfunction "A1_1") (pintype "bidirectional"))
      (node (ref "X-NORTH") (pin "128") (pinfunction "128_128") (pintype "bidirectional"))
    )
    (net (code "83") (name "N39_N") (class "Default")
      (node (ref "U5") (pin "1") (pinfunction "A1_1") (pintype "bidirectional"))
      (node (ref "X-NORTH") (pin "131") (pinfunction "131_131") (pintype "bidirectional"))
    )
    (net (code "84") (name "N39_P") (class "Default")
      (node (ref "U5") (pin "2") (pinfunction "A2_2") (pintype "bidirectional"))
      (node (ref "X-NORTH") (pin "129") (pinfunction "129_129") (pintype "bidirectional"))
    )
    (net (code "85") (name "N_CHK_EN") (class "Default")
      (node (ref "X-NORTH") (pin "8") (pinfunction "8_8") (pintype "bidirectional"))
    )
    (net (code "86") (name "N_CHK_V") (class "Default")
      (node (ref "C2") (pin "1") (pinfunction "1_1") (pintype "passive"))
      (node (ref "C3") (pin "1") (pinfunction "1_1") (pintype "passive"))
      (node (ref "C4") (pin "1") (pinfunction "1_1") (pintype "passive"))
      (node (ref "R19") (pin "1") (pinfunction "1_1") (pintype "passive"))
      (node (ref "TP1") (pin "TP") (pinfunction "TP_TP") (pintype "input"))
      (node (ref "UNE") (pin "8") (pinfunction "VDD_8") (pintype "power_in"))
      (node (ref "UNN") (pin "8") (pinfunction "VDD_8") (pintype "power_in"))
      (node (ref "UNW") (pin "8") (pinfunction "VDD_8") (pintype "power_in"))
      (node (ref "X-NORTH") (pin "10") (pinfunction "10_10") (pintype "bidirectional"))
    )
    (net (code "87") (name "N_I2C_EN") (class "Default")
      (node (ref "X-NORTH") (pin "137") (pinfunction "137_137") (pintype "bidirectional"))
    )
    (net (code "88") (name "N_I2C_V") (class "Default")
      (node (ref "C1") (pin "1") (pinfunction "1_1") (pintype "passive"))
      (node (ref "R1X") (pin "1") (pinfunction "1_1") (pintype "passive"))
      (node (ref "UEP") (pin "8") (pinfunction "VCC_8") (pintype "power_in"))
      (node (ref "X-NORTH") (pin "135") (pinfunction "135_135") (pintype "bidirectional"))
    )
    (net (code "89") (name "N_REF") (class "Default")
      (node (ref "R19") (pin "2") (pinfunction "2_2") (pintype "passive"))
      (node (ref "TP2") (pin "TP") (pinfunction "TP_TP") (pintype "input"))
      (node (ref "U1") (pin "1") (pinfunction "CATHODE_1") (pintype "output"))
      (node (ref "U1") (pin "3") (pinfunction "REF_3") (pintype "input"))
      (node (ref "UNE") (pin "2") (pinfunction "VINA-_2") (pintype "input"))
      (node (ref "UNE") (pin "5") (pinfunction "VINB+_5") (pintype "input"))
      (node (ref "UNN") (pin "2") (pinfunction "VINA-_2") (pintype "input"))
      (node (ref "UNN") (pin "5") (pinfunction "VINB+_5") (pintype "input"))
      (node (ref "UNW") (pin "2") (pinfunction "VINA-_2") (pintype "input"))
      (node (ref "UNW") (pin "5") (pinfunction "VINB+_5") (pintype "input"))
    )
    (net (code "90") (name "N_SCK") (class "Default")
      (node (ref "U4") (pin "4") (pinfunction "A4_4") (pintype "bidirectional"))
      (node (ref "X-NORTH") (pin "144") (pinfunction "144_144") (pintype "bidirectional"))
    )
    (net (code "91") (name "N_SCL") (class "Default")
      (node (ref "UEP") (pin "6") (pinfunction "SCL_6") (pintype "input"))
      (node (ref "X-NORTH") (pin "143") (pinfunction "143_143") (pintype "bidirectional"))
    )
    (net (code "92") (name "N_SDA") (class "Default")
      (node (ref "UEP") (pin "5") (pinfunction "SDA_5") (pintype "bidirectional"))
      (node (ref "X-NORTH") (pin "141") (pinfunction "141_141") (pintype "bidirectional"))
    )
    (net (code "93") (name "N_SDI") (class "Default")
      (node (ref "U4") (pin "2") (pinfunction "A2_2") (pintype "bidirectional"))
      (node (ref "X-NORTH") (pin "140") (pinfunction "140_140") (pintype "bidirectional"))
    )
    (net (code "94") (name "N_SDO") (class "Default")
      (node (ref "U4") (pin "3") (pinfunction "A3_3") (pintype "bidirectional"))
      (node (ref "X-NORTH") (pin "142") (pinfunction "142_142") (pintype "bidirectional"))
    )
    (net (code "95") (name "N_SPI_EN") (class "Default")
      (node (ref "U4") (pin "1") (pinfunction "A1_1") (pintype "bidirectional"))
      (node (ref "X-NORTH") (pin "136") (pinfunction "136_136") (pintype "bidirectional"))
    )
    (net (code "96") (name "N_SPI_V") (class "Default")
      (node (ref "C59") (pin "1") (pinfunction "1_1") (pintype "passive"))
      (node (ref "U4") (pin "14") (pinfunction "VCCA_14") (pintype "power_in"))
      (node (ref "U4") (pin "15") (pinfunction "DIR1_15") (pintype "input"))
      (node (ref "U4") (pin "5") (pinfunction "DIR3_5") (pintype "input"))
      (node (ref "U4") (pin "6") (pinfunction "DIR4_6") (pintype "input"))
      (node (ref "X-NORTH") (pin "134") (pinfunction "134_134") (pintype "bidirectional"))
    )
    (net (code "97") (name "N_VE") (class "Default")
      (node (ref "C22") (pin "1") (pinfunction "1_1") (pintype "passive"))
      (node (ref "C23") (pin "1") (pinfunction "1_1") (pintype "passive"))
      (node (ref "C24") (pin "1") (pinfunction "1_1") (pintype "passive"))
      (node (ref "C25") (pin "1") (pinfunction "1_1") (pintype "passive"))
      (node (ref "C26") (pin "1") (pinfunction "1_1") (pintype "passive"))
      (node (ref "C27") (pin "1") (pinfunction "1_1") (pintype "passive"))
      (node (ref "C28") (pin "1") (pinfunction "1_1") (pintype "passive"))
      (node (ref "C50") (pin "1") (pinfunction "1_1") (pintype "passive"))
      (node (ref "C51") (pin "1") (pinfunction "1_1") (pintype "passive"))
      (node (ref "C52") (pin "1") (pinfunction "1_1") (pintype "passive"))
      (node (ref "C53") (pin "1") (pinfunction "1_1") (pintype "passive"))
      (node (ref "C54") (pin "1") (pinfunction "1_1") (pintype "passive"))
      (node (ref "C55") (pin "1") (pinfunction "1_1") (pintype "passive"))
      (node (ref "C56") (pin "1") (pinfunction "1_1") (pintype "passive"))
      (node (ref "C67") (pin "1") (pinfunction "1_1") (pintype "passive"))
      (node (ref "C69") (pin "1") (pinfunction "1_1") (pintype "passive"))
      (node (ref "C75") (pin "1") (pinfunction "1_1") (pintype "passive"))
      (node (ref "C76") (pin "1") (pinfunction "1_1") (pintype "passive"))
      (node (ref "C77") (pin "1") (pinfunction "1_1") (pintype "passive"))
      (node (ref "C84") (pin "1") (pinfunction "1_1") (pintype "passive"))
      (node (ref "C85") (pin "1") (pinfunction "1_1") (pintype "passive"))
      (node (ref "C86") (pin "1") (pinfunction "1_1") (pintype "passive"))
      (node (ref "C93") (pin "1") (pinfunction "1_1") (pintype "passive"))
      (node (ref "SENSOR") (pin "C26") (pinfunction "VDD33_C26") (pintype "power_in"))
      (node (ref "SENSOR") (pin "C27") (pinfunction "VDD33_C27") (pintype "power_in"))
      (node (ref "SENSOR") (pin "D26") (pinfunction "VDD33_D26") (pintype "power_in"))
      (node (ref "SENSOR") (pin "D3") (pinfunction "VDD33_D3") (pintype "power_in"))
      (node (ref "SENSOR") (pin "E26") (pinfunction "VDD33_E26") (pintype "power_in"))
      (node (ref "SENSOR") (pin "F26") (pinfunction "VDD33_F26") (pintype "power_in"))
      (node (ref "SENSOR") (pin "F5") (pinfunction "VDD33_F5") (pintype "power_in"))
      (node (ref "TP7") (pin "TP") (pinfunction "TP_TP") (pintype "input"))
      (node (ref "U4") (pin "13") (pinfunction "VCCB_13") (pintype "power_in"))
      (node (ref "U5") (pin "13") (pinfunction "VCCB_13") (pintype "power_in"))
      (node (ref "U6") (pin "13") (pinfunction "VCCB_13") (pintype "power_in"))
      (node (ref "X-NORTH") (pin "109") (pinfunction "109_109") (pintype "bidirectional"))
      (node (ref "X-NORTH") (pin "115") (pinfunction "115_115") (pintype "bidirectional"))
      (node (ref "X-NORTH") (pin "121") (pinfunction "121_121") (pintype "bidirectional"))
      (node (ref "X-NORTH") (pin "127") (pinfunction "127_127") (pintype "bidirectional"))
      (node (ref "X-NORTH") (pin "133") (pinfunction "133_133") (pintype "bidirectional"))
    )
    (net (code "98") (name "N_VE_CV") (class "Default")
      (node (ref "C10") (pin "1") (pinfunction "1_1") (pintype "passive"))
      (node (ref "R7") (pin "1") (pinfunction "1_1") (pintype "passive"))
      (node (ref "X-NORTH") (pin "6") (pinfunction "6_6") (pintype "bidirectional"))
    )
    (net (code "99") (name "N_VE_OV") (class "Default")
      (node (ref "UNE") (pin "7") (pinfunction "OUTB_7") (pintype "output"))
      (node (ref "X-NORTH") (pin "5") (pinfunction "5_5") (pintype "bidirectional"))
    )
    (net (code "100") (name "N_VE_UV") (class "Default")
      (node (ref "UNE") (pin "1") (pinfunction "OUTA_1") (pintype "output"))
      (node (ref "X-NORTH") (pin "11") (pinfunction "11_11") (pintype "bidirectional"))
    )
    (net (code "101") (name "N_VN") (class "Default")
      (node (ref "C31") (pin "1") (pinfunction "1_1") (pintype "passive"))
      (node (ref "C32") (pin "1") (pinfunction "1_1") (pintype "passive"))
      (node (ref "C33") (pin "1") (pinfunction "1_1") (pintype "passive"))
      (node (ref "C34") (pin "1") (pinfunction "1_1") (pintype "passive"))
      (node (ref "C35") (pin "1") (pinfunction "1_1") (pintype "passive"))
      (node (ref "C36") (pin "1") (pinfunction "1_1") (pintype "passive"))
      (node (ref "C37") (pin "1") (pinfunction "1_1") (pintype "passive"))
      (node (ref "C38") (pin "1") (pinfunction "1_1") (pintype "passive"))
      (node (ref "C39") (pin "1") (pinfunction "1_1") (pintype "passive"))
      (node (ref "C40") (pin "1") (pinfunction "1_1") (pintype "passive"))
      (node (ref "C41") (pin "1") (pinfunction "1_1") (pintype "passive"))
      (node (ref "C42") (pin "1") (pinfunction "1_1") (pintype "passive"))
      (node (ref "C43") (pin "1") (pinfunction "1_1") (pintype "passive"))
      (node (ref "C44") (pin "1") (pinfunction "1_1") (pintype "passive"))
      (node (ref "C68") (pin "1") (pinfunction "1_1") (pintype "passive"))
      (node (ref "C70") (pin "1") (pinfunction "1_1") (pintype "passive"))
      (node (ref "C78") (pin "1") (pinfunction "1_1") (pintype "passive"))
      (node (ref "C79") (pin "1") (pinfunction "1_1") (pintype "passive"))
      (node (ref "C80") (pin "1") (pinfunction "1_1") (pintype "passive"))
      (node (ref "C87") (pin "1") (pinfunction "1_1") (pintype "passive"))
      (node (ref "C88") (pin "1") (pinfunction "1_1") (pintype "passive"))
      (node (ref "C89") (pin "1") (pinfunction "1_1") (pintype "passive"))
      (node (ref "SENSOR") (pin "A10") (pinfunction "VDD18_A10") (pintype "power_in"))
      (node (ref "SENSOR") (pin "A15") (pinfunction "VDD18_A15") (pintype "power_in"))
      (node (ref "SENSOR") (pin "A16") (pinfunction "VDD18_A16") (pintype "power_in"))
      (node (ref "SENSOR") (pin "A22") (pinfunction "VDD18_A22") (pintype "power_in"))
      (node (ref "SENSOR") (pin "A26") (pinfunction "VDD18_A26") (pintype "power_in"))
      (node (ref "SENSOR") (pin "A27") (pinfunction "VDD18_A27") (pintype "power_in"))
      (node (ref "SENSOR") (pin "B4") (pinfunction "VDD18_B4") (pintype "power_in"))
      (node (ref "SENSOR") (pin "E1") (pinfunction "VDD18_PLL_E1") (pintype "power_in"))
      (node (ref "SENSOR") (pin "H10") (pinfunction "VDD18_H10") (pintype "power_in"))
      (node (ref "SENSOR") (pin "H15") (pinfunction "VDD18_H15") (pintype "power_in"))
      (node (ref "SENSOR") (pin "H16") (pinfunction "VDD18_H16") (pintype "power_in"))
      (node (ref "SENSOR") (pin "H22") (pinfunction "VDD18_H22") (pintype "power_in"))
      (node (ref "SENSOR") (pin "H26") (pinfunction "VDD18_H26") (pintype "power_in"))
      (node (ref "SENSOR") (pin "H5") (pinfunction "VDD18_H5") (pintype "power_in"))
      (node (ref "TP5") (pin "TP") (pinfunction "TP_TP") (pintype "input"))
      (node (ref "U5") (pin "14") (pinfunction "VCCA_14") (pintype "power_in"))
      (node (ref "U5") (pin "15") (pinfunction "DIR1_15") (pintype "input"))
      (node (ref "U5") (pin "16") (pinfunction "DIR2_16") (pintype "input"))
      (node (ref "U5") (pin "5") (pinfunction "DIR3_5") (pintype "input"))
      (node (ref "U6") (pin "14") (pinfunction "VCCA_14") (pintype "power_in"))
      (node (ref "U6") (pin "15") (pinfunction "DIR1_15") (pintype "input"))
      (node (ref "U6") (pin "5") (pinfunction "DIR3_5") (pintype "input"))
      (node (ref "U6") (pin "6") (pinfunction "DIR4_6") (pintype "input"))
      (node (ref "X-NORTH") (pin "49") (pinfunction "49_49") (pintype "bidirectional"))
      (node (ref "X-NORTH") (pin "55") (pinfunction "55_55") (pintype "bidirectional"))
      (node (ref "X-NORTH") (pin "61") (pinfunction "61_61") (pintype "bidirectional"))
      (node (ref "X-NORTH") (pin "67") (pinfunction "67_67") (pintype "bidirectional"))
      (node (ref "X-NORTH") (pin "73") (pinfunction "73_73") (pintype "bidirectional"))
      (node (ref "X-NORTH") (pin "79") (pinfunction "79_79") (pintype "bidirectional"))
      (node (ref "X-NORTH") (pin "85") (pinfunction "85_85") (pintype "bidirectional"))
      (node (ref "X-NORTH") (pin "91") (pinfunction "91_91") (pintype "bidirectional"))
      (node (ref "X-NORTH") (pin "97") (pinfunction "97_97") (pintype "bidirectional"))
    )
    (net (code "102") (name "N_VN_CV") (class "Default")
      (node (ref "C9") (pin "1") (pinfunction "1_1") (pintype "passive"))
      (node (ref "R4") (pin "1") (pinfunction "1_1") (pintype "passive"))
      (node (ref "X-NORTH") (pin "4") (pinfunction "4_4") (pintype "bidirectional"))
    )
    (net (code "103") (name "N_VN_OV") (class "Default")
      (node (ref "UNN") (pin "7") (pinfunction "OUTB_7") (pintype "output"))
      (node (ref "X-NORTH") (pin "3") (pinfunction "3_3") (pintype "bidirectional"))
    )
    (net (code "104") (name "N_VN_UV") (class "Default")
      (node (ref "UNN") (pin "1") (pinfunction "OUTA_1") (pintype "output"))
      (node (ref "X-NORTH") (pin "9") (pinfunction "9_9") (pintype "bidirectional"))
    )
    (net (code "105") (name "N_VW") (class "Default")
      (node (ref "C57") (pin "1") (pinfunction "1_1") (pintype "passive"))
      (node (ref "C58") (pin "1") (pinfunction "1_1") (pintype "passive"))
      (node (ref "C92") (pin "1") (pinfunction "1_1") (pintype "passive"))
      (node (ref "SENSOR") (pin "E2") (pinfunction "VDD_RES_E2") (pintype "power_in"))
      (node (ref "SENSOR") (pin "G4") (pinfunction "VDD_RES_G4") (pintype "power_in"))
      (node (ref "TP8") (pin "TP") (pinfunction "TP_TP") (pintype "input"))
      (node (ref "X-NORTH") (pin "13") (pinfunction "13_13") (pintype "bidirectional"))
      (node (ref "X-NORTH") (pin "19") (pinfunction "19_19") (pintype "bidirectional"))
      (node (ref "X-NORTH") (pin "25") (pinfunction "25_25") (pintype "bidirectional"))
      (node (ref "X-NORTH") (pin "31") (pinfunction "31_31") (pintype "bidirectional"))
      (node (ref "X-NORTH") (pin "37") (pinfunction "37_37") (pintype "bidirectional"))
    )
    (net (code "106") (name "N_VW_CV") (class "Default")
      (node (ref "C8") (pin "1") (pinfunction "1_1") (pintype "passive"))
      (node (ref "R1") (pin "1") (pinfunction "1_1") (pintype "passive"))
      (node (ref "X-NORTH") (pin "2") (pinfunction "2_2") (pintype "bidirectional"))
    )
    (net (code "107") (name "N_VW_OV") (class "Default")
      (node (ref "UNW") (pin "7") (pinfunction "OUTB_7") (pintype "output"))
      (node (ref "X-NORTH") (pin "1") (pinfunction "1_1") (pintype "bidirectional"))
    )
    (net (code "108") (name "N_VW_UV") (class "Default")
      (node (ref "UNW") (pin "1") (pinfunction "OUTA_1") (pintype "output"))
      (node (ref "X-NORTH") (pin "7") (pinfunction "7_7") (pintype "bidirectional"))
    )
    (net (code "109") (name "Net-(SENSORB-CMDN)") (class "Default")
      (node (ref "C61") (pin "1") (pinfunction "1_1") (pintype "passive"))
      (node (ref "SENSOR") (pin "F1") (pinfunction "CMDN_F1") (pintype "bidirectional"))
    )
    (net (code "110") (name "Net-(SENSORB-CMDP)") (class "Default")
      (node (ref "C22") (pin "2") (pinfunction "2_2") (pintype "passive"))
      (node (ref "SENSOR") (pin "F2") (pinfunction "CMDP_F2") (pintype "bidirectional"))
    )
    (net (code "111") (name "Net-(SENSORB-CMDP_COMP)") (class "Default")
      (node (ref "C28") (pin "2") (pinfunction "2_2") (pintype "passive"))
      (node (ref "SENSOR") (pin "H3") (pinfunction "CMDP_COMP_H3") (pintype "bidirectional"))
    )
    (net (code "112") (name "Net-(SENSORB-CMDP_COMP_INV)") (class "Default")
      (node (ref "C27") (pin "2") (pinfunction "2_2") (pintype "passive"))
      (node (ref "SENSOR") (pin "F3") (pinfunction "CMDP_COMP_INV_F3") (pintype "bidirectional"))
    )
    (net (code "113") (name "Net-(SENSORB-CMD_COLAMP)") (class "Default")
      (node (ref "C25") (pin "2") (pinfunction "2_2") (pintype "passive"))
      (node (ref "SENSOR") (pin "C6") (pinfunction "CMD_COLAMP_C6") (pintype "bidirectional"))
    )
    (net (code "114") (name "Net-(SENSORB-CMD_COL_LOAD)") (class "Default")
      (node (ref "C23") (pin "2") (pinfunction "2_2") (pintype "passive"))
      (node (ref "SENSOR") (pin "B1") (pinfunction "CMD_COL_LOAD_B1") (pintype "bidirectional"))
    )
    (net (code "115") (name "Net-(SENSORB-CMD_COL_PC)") (class "Default")
      (node (ref "C26") (pin "2") (pinfunction "2_2") (pintype "passive"))
      (node (ref "SENSOR") (pin "D1") (pinfunction "CMD_COL_PC_D1") (pintype "bidirectional"))
    )
    (net (code "116") (name "Net-(SENSORB-CMD_LVDS)") (class "Default")
      (node (ref "C62") (pin "1") (pinfunction "1_1") (pintype "passive"))
      (node (ref "SENSOR") (pin "C1") (pinfunction "CMD_LVDS_C1") (pintype "bidirectional"))
    )
    (net (code "117") (name "Net-(SENSORB-CMD_RAMP)") (class "Default")
      (node (ref "C24") (pin "2") (pinfunction "2_2") (pintype "passive"))
      (node (ref "SENSOR") (pin "B29") (pinfunction "CMD_RAMP_B29") (pintype "bidirectional"))
    )
    (net (code "118") (name "Net-(SENSORB-VBGAP)") (class "Default")
      (node (ref "C64") (pin "1") (pinfunction "1_1") (pintype "passive"))
      (node (ref "SENSOR") (pin "C29") (pinfunction "VBGAP_C29") (pintype "bidirectional"))
    )
    (net (code "119") (name "Net-(SENSORB-VCLAMP)") (class "Default")
      (node (ref "C63") (pin "1") (pinfunction "1_1") (pintype "passive"))
      (node (ref "SENSOR") (pin "D4") (pinfunction "VCLAMP_D4") (pintype "bidirectional"))
    )
    (net (code "120") (name "Net-(SENSORB-VCLAMP_ADC)") (class "Default")
      (node (ref "C60") (pin "1") (pinfunction "1_1") (pintype "passive"))
      (node (ref "SENSOR") (pin "G2") (pinfunction "VCLAMP_ADC_G2") (pintype "bidirectional"))
    )
    (net (code "121") (name "Net-(SENSORB-VPCH_H)") (class "Default")
      (node (ref "C71") (pin "1") (pinfunction "1_1") (pintype "passive"))
      (node (ref "SENSOR") (pin "C4") (pinfunction "VPCH_H_C4") (pintype "bidirectional"))
    )
    (net (code "122") (name "Net-(SENSORB-VPCH_L)") (class "Default")
      (node (ref "C14") (pin "1") (pinfunction "1_1") (pintype "passive"))
      (node (ref "SENSOR") (pin "A4") (pinfunction "VPCH_L_A4") (pintype "bidirectional"))
    )
    (net (code "123") (name "Net-(SENSORB-VREF)") (class "Default")
      (node (ref "C29") (pin "1") (pinfunction "1_1") (pintype "passive"))
      (node (ref "SENSOR") (pin "A3") (pinfunction "VREF_A3") (pintype "bidirectional"))
    )
    (net (code "124") (name "Net-(SENSORB-VREF_ADC)") (class "Default")
      (node (ref "C30") (pin "1") (pinfunction "1_1") (pintype "passive"))
      (node (ref "SENSOR") (pin "B3") (pinfunction "VREF_ADC_B3") (pintype "bidirectional"))
    )
    (net (code "125") (name "Net-(SENSORB-VRES_L)") (class "Default")
      (node (ref "C15") (pin "1") (pinfunction "1_1") (pintype "passive"))
      (node (ref "SENSOR") (pin "D5") (pinfunction "VRES_L_D5") (pintype "bidirectional"))
    )
    (net (code "126") (name "Net-(SENSORB-VTF_LOW0)") (class "Default")
      (node (ref "C18") (pin "1") (pinfunction "1_1") (pintype "passive"))
      (node (ref "SENSOR") (pin "C5") (pinfunction "VTF_LOW0_C5") (pintype "bidirectional"))
    )
    (net (code "127") (name "Net-(SENSORB-VTF_LOW1)") (class "Default")
      (node (ref "C19") (pin "1") (pinfunction "1_1") (pintype "passive"))
      (node (ref "SENSOR") (pin "D6") (pinfunction "VTF_LOW1_D6") (pintype "bidirectional"))
    )
    (net (code "128") (name "Net-(SENSORB-VTF_LOW2)") (class "Default")
      (node (ref "C20") (pin "1") (pinfunction "1_1") (pintype "passive"))
      (node (ref "SENSOR") (pin "B30") (pinfunction "VTF_LOW2_B30") (pintype "bidirectional"))
    )
    (net (code "129") (name "Net-(SENSORB-VTF_LOW3)") (class "Default")
      (node (ref "C21") (pin "1") (pinfunction "1_1") (pintype "passive"))
      (node (ref "SENSOR") (pin "C30") (pinfunction "VTF_LOW3_C30") (pintype "bidirectional"))
    )
    (net (code "130") (name "Net-(U3-ADJ)") (class "Default")
      (node (ref "R21") (pin "1") (pinfunction "1_1") (pintype "passive"))
      (node (ref "R22") (pin "2") (pinfunction "2_2") (pintype "passive"))
      (node (ref "U3") (pin "5") (pinfunction "ADJ_5") (pintype "input"))
    )
    (net (code "131") (name "Net-(U6-B4)") (class "Default")
      (node (ref "TP9") (pin "TP") (pinfunction "TP_TP") (pintype "input"))
      (node (ref "U6") (pin "9") (pinfunction "B4_9") (pintype "bidirectional"))
    )
    (net (code "132") (name "Net-(UEP-WP)") (class "Default")
      (node (ref "R1X") (pin "2") (pinfunction "2_2") (pintype "passive"))
      (node (ref "R2X") (pin "1") (pinfunction "1_1") (pintype "passive"))
      (node (ref "UEP") (pin "7") (pinfunction "WP_7") (pintype "input"))
    )
    (net (code "133") (name "Net-(UNE-VINA+)") (class "Default")
      (node (ref "R7") (pin "2") (pinfunction "2_2") (pintype "passive"))
      (node (ref "R8") (pin "1") (pinfunction "1_1") (pintype "passive"))
      (node (ref "UNE") (pin "3") (pinfunction "VINA+_3") (pintype "input"))
    )
    (net (code "134") (name "Net-(UNE-VINB-)") (class "Default")
      (node (ref "R8") (pin "2") (pinfunction "2_2") (pintype "passive"))
      (node (ref "R9") (pin "1") (pinfunction "1_1") (pintype "passive"))
      (node (ref "UNE") (pin "6") (pinfunction "VINB-_6") (pintype "input"))
    )
    (net (code "135") (name "Net-(UNN-VINA+)") (class "Default")
      (node (ref "R4") (pin "2") (pinfunction "2_2") (pintype "passive"))
      (node (ref "R5") (pin "1") (pinfunction "1_1") (pintype "passive"))
      (node (ref "UNN") (pin "3") (pinfunction "VINA+_3") (pintype "input"))
    )
    (net (code "136") (name "Net-(UNN-VINB-)") (class "Default")
      (node (ref "R5") (pin "2") (pinfunction "2_2") (pintype "passive"))
      (node (ref "R6") (pin "1") (pinfunction "1_1") (pintype "passive"))
      (node (ref "UNN") (pin "6") (pinfunction "VINB-_6") (pintype "input"))
    )
    (net (code "137") (name "Net-(UNW-VINA+)") (class "Default")
      (node (ref "R1") (pin "2") (pinfunction "2_2") (pintype "passive"))
      (node (ref "R2") (pin "1") (pinfunction "1_1") (pintype "passive"))
      (node (ref "UNW") (pin "3") (pinfunction "VINA+_3") (pintype "input"))
    )
    (net (code "138") (name "Net-(UNW-VINB-)") (class "Default")
      (node (ref "R2") (pin "2") (pinfunction "2_2") (pintype "passive"))
      (node (ref "R3") (pin "1") (pinfunction "1_1") (pintype "passive"))
      (node (ref "UNW") (pin "6") (pinfunction "VINB-_6") (pintype "input"))
    )
    (net (code "139") (name "Net-(USE-VINA+)") (class "Default")
      (node (ref "R10") (pin "2") (pinfunction "2_2") (pintype "passive"))
      (node (ref "R11") (pin "1") (pinfunction "1_1") (pintype "passive"))
      (node (ref "USE") (pin "3") (pinfunction "VINA+_3") (pintype "input"))
    )
    (net (code "140") (name "Net-(USE-VINB-)") (class "Default")
      (node (ref "R11") (pin "2") (pinfunction "2_2") (pintype "passive"))
      (node (ref "R12") (pin "1") (pinfunction "1_1") (pintype "passive"))
      (node (ref "USE") (pin "6") (pinfunction "VINB-_6") (pintype "input"))
    )
    (net (code "141") (name "Net-(USS-VINA+)") (class "Default")
      (node (ref "R13") (pin "2") (pinfunction "2_2") (pintype "passive"))
      (node (ref "R14") (pin "1") (pinfunction "1_1") (pintype "passive"))
      (node (ref "USS") (pin "3") (pinfunction "VINA+_3") (pintype "input"))
    )
    (net (code "142") (name "Net-(USS-VINB-)") (class "Default")
      (node (ref "R14") (pin "2") (pinfunction "2_2") (pintype "passive"))
      (node (ref "R15") (pin "1") (pinfunction "1_1") (pintype "passive"))
      (node (ref "USS") (pin "6") (pinfunction "VINB-_6") (pintype "input"))
    )
    (net (code "143") (name "Net-(USW-VINA+)") (class "Default")
      (node (ref "R16") (pin "2") (pinfunction "2_2") (pintype "passive"))
      (node (ref "R17") (pin "1") (pinfunction "1_1") (pintype "passive"))
      (node (ref "USW") (pin "3") (pinfunction "VINA+_3") (pintype "input"))
    )
    (net (code "144") (name "Net-(USW-VINB-)") (class "Default")
      (node (ref "R17") (pin "2") (pinfunction "2_2") (pintype "passive"))
      (node (ref "R18") (pin "1") (pinfunction "1_1") (pintype "passive"))
      (node (ref "USW") (pin "6") (pinfunction "VINB-_6") (pintype "input"))
    )
    (net (code "145") (name "S00_N") (class "Default")
      (node (ref "X-SOUTH") (pin "16") (pinfunction "16_16") (pintype "bidirectional"))
    )
    (net (code "146") (name "S00_P") (class "Default")
      (node (ref "X-SOUTH") (pin "14") (pinfunction "14_14") (pintype "bidirectional"))
    )
    (net (code "147") (name "S01_N") (class "Default")
      (node (ref "X-SOUTH") (pin "17") (pinfunction "17_17") (pintype "bidirectional"))
    )
    (net (code "148") (name "S01_P") (class "Default")
      (node (ref "X-SOUTH") (pin "15") (pinfunction "15_15") (pintype "bidirectional"))
    )
    (net (code "149") (name "S02_N") (class "Default")
      (node (ref "X-SOUTH") (pin "22") (pinfunction "22_22") (pintype "bidirectional"))
    )
    (net (code "150") (name "S02_P") (class "Default")
      (node (ref "X-SOUTH") (pin "20") (pinfunction "20_20") (pintype "bidirectional"))
    )
    (net (code "151") (name "S03_N") (class "Default")
      (node (ref "X-SOUTH") (pin "23") (pinfunction "23_23") (pintype "bidirectional"))
    )
    (net (code "152") (name "S03_P") (class "Default")
      (node (ref "X-SOUTH") (pin "21") (pinfunction "21_21") (pintype "bidirectional"))
    )
    (net (code "153") (name "S04_N") (class "Default")
      (node (ref "SENSOR") (pin "C24") (pinfunction "OUT32_N_C24") (pintype "output"))
      (node (ref "X-SOUTH") (pin "28") (pinfunction "28_28") (pintype "bidirectional"))
    )
    (net (code "154") (name "S04_P") (class "Default")
      (node (ref "SENSOR") (pin "C25") (pinfunction "OUT32_P_C25") (pintype "output"))
      (node (ref "X-SOUTH") (pin "26") (pinfunction "26_26") (pintype "bidirectional"))
    )
    (net (code "155") (name "S05_N") (class "Default")
      (node (ref "X-SOUTH") (pin "29") (pinfunction "29_29") (pintype "bidirectional"))
    )
    (net (code "156") (name "S05_P") (class "Default")
      (node (ref "X-SOUTH") (pin "27") (pinfunction "27_27") (pintype "bidirectional"))
    )
    (net (code "157") (name "S06_N") (class "Default")
      (node (ref "SENSOR") (pin "D23") (pinfunction "OUT30_N_D23") (pintype "output"))
      (node (ref "X-SOUTH") (pin "34") (pinfunction "34_34") (pintype "bidirectional"))
    )
    (net (code "158") (name "S06_P") (class "Default")
      (node (ref "SENSOR") (pin "D24") (pinfunction "OUT30_P_D24") (pintype "output"))
      (node (ref "X-SOUTH") (pin "32") (pinfunction "32_32") (pintype "bidirectional"))
    )
    (net (code "159") (name "S07_N") (class "Default")
      (node (ref "SENSOR") (pin "B24") (pinfunction "OUT31_N_B24") (pintype "output"))
      (node (ref "X-SOUTH") (pin "35") (pinfunction "35_35") (pintype "bidirectional"))
    )
    (net (code "160") (name "S07_P") (class "Default")
      (node (ref "SENSOR") (pin "B25") (pinfunction "OUT31_P_B25") (pintype "output"))
      (node (ref "X-SOUTH") (pin "33") (pinfunction "33_33") (pintype "bidirectional"))
    )
    (net (code "161") (name "S08_N") (class "Default")
      (node (ref "SENSOR") (pin "D21") (pinfunction "OUT27_N_D21") (pintype "output"))
      (node (ref "X-SOUTH") (pin "40") (pinfunction "40_40") (pintype "bidirectional"))
    )
    (net (code "162") (name "S08_P") (class "Default")
      (node (ref "SENSOR") (pin "D22") (pinfunction "OUT27_P_D22") (pintype "output"))
      (node (ref "X-SOUTH") (pin "38") (pinfunction "38_38") (pintype "bidirectional"))
    )
    (net (code "163") (name "S09_N") (class "Default")
      (node (ref "SENSOR") (pin "A23") (pinfunction "OUT29_N_A23") (pintype "output"))
      (node (ref "X-SOUTH") (pin "41") (pinfunction "41_41") (pintype "bidirectional"))
    )
    (net (code "164") (name "S09_P") (class "Default")
      (node (ref "SENSOR") (pin "A24") (pinfunction "OUT29_P_A24") (pintype "output"))
      (node (ref "X-SOUTH") (pin "39") (pinfunction "39_39") (pintype "bidirectional"))
    )
    (net (code "165") (name "S10_N") (class "Default")
      (node (ref "SENSOR") (pin "C21") (pinfunction "OUT28_N_C21") (pintype "output"))
      (node (ref "X-SOUTH") (pin "46") (pinfunction "46_46") (pintype "bidirectional"))
    )
    (net (code "166") (name "S10_P") (class "Default")
      (node (ref "SENSOR") (pin "C22") (pinfunction "OUT28_P_C22") (pintype "output"))
      (node (ref "X-SOUTH") (pin "44") (pinfunction "44_44") (pintype "bidirectional"))
    )
    (net (code "167") (name "S11_N") (class "Default")
      (node (ref "SENSOR") (pin "B20") (pinfunction "OUT26_N_B20") (pintype "output"))
      (node (ref "X-SOUTH") (pin "47") (pinfunction "47_47") (pintype "bidirectional"))
    )
    (net (code "168") (name "S11_P") (class "Default")
      (node (ref "SENSOR") (pin "B21") (pinfunction "OUT26_P_B21") (pintype "output"))
      (node (ref "X-SOUTH") (pin "45") (pinfunction "45_45") (pintype "bidirectional"))
    )
    (net (code "169") (name "S12_N") (class "Default")
      (node (ref "SENSOR") (pin "D19") (pinfunction "OUT24_N_D19") (pintype "output"))
      (node (ref "X-SOUTH") (pin "52") (pinfunction "52_52") (pintype "bidirectional"))
    )
    (net (code "170") (name "S12_P") (class "Default")
      (node (ref "SENSOR") (pin "D20") (pinfunction "OUT24_P_D20") (pintype "output"))
      (node (ref "X-SOUTH") (pin "50") (pinfunction "50_50") (pintype "bidirectional"))
    )
    (net (code "171") (name "S13_N") (class "Default")
      (node (ref "SENSOR") (pin "A19") (pinfunction "OUT23_N_A19") (pintype "output"))
      (node (ref "X-SOUTH") (pin "53") (pinfunction "53_53") (pintype "bidirectional"))
    )
    (net (code "172") (name "S13_P") (class "Default")
      (node (ref "SENSOR") (pin "A20") (pinfunction "OUT23_P_A20") (pintype "output"))
      (node (ref "X-SOUTH") (pin "51") (pinfunction "51_51") (pintype "bidirectional"))
    )
    (net (code "173") (name "S14_N") (class "Default")
      (node (ref "SENSOR") (pin "C19") (pinfunction "OUT25_N_C19") (pintype "output"))
      (node (ref "X-SOUTH") (pin "58") (pinfunction "58_58") (pintype "bidirectional"))
    )
    (net (code "174") (name "S14_P") (class "Default")
      (node (ref "SENSOR") (pin "C20") (pinfunction "OUT25_P_C20") (pintype "output"))
      (node (ref "X-SOUTH") (pin "56") (pinfunction "56_56") (pintype "bidirectional"))
    )
    (net (code "175") (name "S15_N") (class "Default")
      (node (ref "SENSOR") (pin "B18") (pinfunction "OUT22_N_B18") (pintype "output"))
      (node (ref "X-SOUTH") (pin "59") (pinfunction "59_59") (pintype "bidirectional"))
    )
    (net (code "176") (name "S15_P") (class "Default")
      (node (ref "SENSOR") (pin "B19") (pinfunction "OUT22_P_B19") (pintype "output"))
      (node (ref "X-SOUTH") (pin "57") (pinfunction "57_57") (pintype "bidirectional"))
    )
    (net (code "177") (name "S16_N") (class "Default")
      (node (ref "SENSOR") (pin "C17") (pinfunction "OUT21_N_C17") (pintype "output"))
      (node (ref "X-SOUTH") (pin "64") (pinfunction "64_64") (pintype "bidirectional"))
    )
    (net (code "178") (name "S16_P") (class "Default")
      (node (ref "SENSOR") (pin "C18") (pinfunction "OUT21_P_C18") (pintype "output"))
      (node (ref "X-SOUTH") (pin "62") (pinfunction "62_62") (pintype "bidirectional"))
    )
    (net (code "179") (name "S17_N") (class "Default")
      (node (ref "SENSOR") (pin "A17") (pinfunction "OUT19_N_A17") (pintype "output"))
      (node (ref "X-SOUTH") (pin "65") (pinfunction "65_65") (pintype "bidirectional"))
    )
    (net (code "180") (name "S17_P") (class "Default")
      (node (ref "SENSOR") (pin "A18") (pinfunction "OUT19_P_A18") (pintype "output"))
      (node (ref "X-SOUTH") (pin "63") (pinfunction "63_63") (pintype "bidirectional"))
    )
    (net (code "181") (name "S18_N") (class "Default")
      (node (ref "SENSOR") (pin "D17") (pinfunction "OUT20_N_D17") (pintype "output"))
      (node (ref "X-SOUTH") (pin "70") (pinfunction "70_70") (pintype "bidirectional"))
    )
    (net (code "182") (name "S18_P") (class "Default")
      (node (ref "SENSOR") (pin "D18") (pinfunction "OUT20_P_D18") (pintype "output"))
      (node (ref "X-SOUTH") (pin "68") (pinfunction "68_68") (pintype "bidirectional"))
    )
    (net (code "183") (name "S19_N") (class "Default")
      (node (ref "SENSOR") (pin "B16") (pinfunction "OUT18_N_B16") (pintype "output"))
      (node (ref "X-SOUTH") (pin "71") (pinfunction "71_71") (pintype "bidirectional"))
    )
    (net (code "184") (name "S19_P") (class "Default")
      (node (ref "SENSOR") (pin "B17") (pinfunction "OUT18_P_B17") (pintype "output"))
      (node (ref "X-SOUTH") (pin "69") (pinfunction "69_69") (pintype "bidirectional"))
    )
    (net (code "185") (name "S20_N") (class "Default")
      (node (ref "SENSOR") (pin "D15") (pinfunction "OUT17_N_D15") (pintype "output"))
      (node (ref "X-SOUTH") (pin "76") (pinfunction "76_76") (pintype "bidirectional"))
    )
    (net (code "186") (name "S20_P") (class "Default")
      (node (ref "SENSOR") (pin "D16") (pinfunction "OUT17_P_D16") (pintype "output"))
      (node (ref "X-SOUTH") (pin "74") (pinfunction "74_74") (pintype "bidirectional"))
    )
    (net (code "187") (name "S21_N") (class "Default")
      (node (ref "SENSOR") (pin "B14") (pinfunction "OUT16_N_B14") (pintype "output"))
      (node (ref "X-SOUTH") (pin "77") (pinfunction "77_77") (pintype "bidirectional"))
    )
    (net (code "188") (name "S21_P") (class "Default")
      (node (ref "SENSOR") (pin "B15") (pinfunction "OUT16_P_B15") (pintype "output"))
      (node (ref "X-SOUTH") (pin "75") (pinfunction "75_75") (pintype "bidirectional"))
    )
    (net (code "189") (name "S22_N") (class "Default")
      (node (ref "SENSOR") (pin "D13") (pinfunction "OUT15_N_D13") (pintype "output"))
      (node (ref "X-SOUTH") (pin "82") (pinfunction "82_82") (pintype "bidirectional"))
    )
    (net (code "190") (name "S22_P") (class "Default")
      (node (ref "SENSOR") (pin "D14") (pinfunction "OUT15_P_D14") (pintype "output"))
      (node (ref "X-SOUTH") (pin "80") (pinfunction "80_80") (pintype "bidirectional"))
    )
    (net (code "191") (name "S23_N") (class "Default")
      (node (ref "SENSOR") (pin "A13") (pinfunction "OUT13_N_A13") (pintype "output"))
      (node (ref "X-SOUTH") (pin "83") (pinfunction "83_83") (pintype "bidirectional"))
    )
    (net (code "192") (name "S23_P") (class "Default")
      (node (ref "SENSOR") (pin "A14") (pinfunction "OUT13_P_A14") (pintype "output"))
      (node (ref "X-SOUTH") (pin "81") (pinfunction "81_81") (pintype "bidirectional"))
    )
    (net (code "193") (name "S24_N") (class "Default")
      (node (ref "SENSOR") (pin "C13") (pinfunction "OUT14_N_C13") (pintype "output"))
      (node (ref "X-SOUTH") (pin "88") (pinfunction "88_88") (pintype "bidirectional"))
    )
    (net (code "194") (name "S24_P") (class "Default")
      (node (ref "SENSOR") (pin "C14") (pinfunction "OUT14_P_C14") (pintype "output"))
      (node (ref "X-SOUTH") (pin "86") (pinfunction "86_86") (pintype "bidirectional"))
    )
    (net (code "195") (name "S25_N") (class "Default")
      (node (ref "SENSOR") (pin "B12") (pinfunction "OUT12_N_B12") (pintype "output"))
      (node (ref "X-SOUTH") (pin "89") (pinfunction "89_89") (pintype "bidirectional"))
    )
    (net (code "196") (name "S25_P") (class "Default")
      (node (ref "SENSOR") (pin "B13") (pinfunction "OUT12_P_B13") (pintype "output"))
      (node (ref "X-SOUTH") (pin "87") (pinfunction "87_87") (pintype "bidirectional"))
    )
    (net (code "197") (name "S26_N") (class "Default")
      (node (ref "SENSOR") (pin "D11") (pinfunction "OUT10_N_D11") (pintype "output"))
      (node (ref "X-SOUTH") (pin "94") (pinfunction "94_94") (pintype "bidirectional"))
    )
    (net (code "198") (name "S26_P") (class "Default")
      (node (ref "SENSOR") (pin "D12") (pinfunction "OUT10_P_D12") (pintype "output"))
      (node (ref "X-SOUTH") (pin "92") (pinfunction "92_92") (pintype "bidirectional"))
    )
    (net (code "199") (name "S27_N") (class "Default")
      (node (ref "SENSOR") (pin "A11") (pinfunction "OUT9_N_A11") (pintype "output"))
      (node (ref "X-SOUTH") (pin "95") (pinfunction "95_95") (pintype "bidirectional"))
    )
    (net (code "200") (name "S27_P") (class "Default")
      (node (ref "SENSOR") (pin "A12") (pinfunction "OUT9_P_A12") (pintype "output"))
      (node (ref "X-SOUTH") (pin "93") (pinfunction "93_93") (pintype "bidirectional"))
    )
    (net (code "201") (name "S28_N") (class "Default")
      (node (ref "SENSOR") (pin "C11") (pinfunction "OUT11_N_C11") (pintype "output"))
      (node (ref "X-SOUTH") (pin "100") (pinfunction "100_100") (pintype "bidirectional"))
    )
    (net (code "202") (name "S28_P") (class "Default")
      (node (ref "SENSOR") (pin "C12") (pinfunction "OUT11_P_C12") (pintype "output"))
      (node (ref "X-SOUTH") (pin "98") (pinfunction "98_98") (pintype "bidirectional"))
    )
    (net (code "203") (name "S29_N") (class "Default")
      (node (ref "SENSOR") (pin "B10") (pinfunction "OUT8_N_B10") (pintype "output"))
      (node (ref "X-SOUTH") (pin "101") (pinfunction "101_101") (pintype "bidirectional"))
    )
    (net (code "204") (name "S29_P") (class "Default")
      (node (ref "SENSOR") (pin "B11") (pinfunction "OUT8_P_B11") (pintype "output"))
      (node (ref "X-SOUTH") (pin "99") (pinfunction "99_99") (pintype "bidirectional"))
    )
    (net (code "205") (name "S30_N") (class "Default")
      (node (ref "SENSOR") (pin "C9") (pinfunction "OUT7_N_C9") (pintype "output"))
      (node (ref "X-SOUTH") (pin "106") (pinfunction "106_106") (pintype "bidirectional"))
    )
    (net (code "206") (name "S30_P") (class "Default")
      (node (ref "SENSOR") (pin "C10") (pinfunction "OUT7_P_C10") (pintype "output"))
      (node (ref "X-SOUTH") (pin "104") (pinfunction "104_104") (pintype "bidirectional"))
    )
    (net (code "207") (name "S31_N") (class "Default")
      (node (ref "SENSOR") (pin "B8") (pinfunction "OUT5_N_B8") (pintype "output"))
      (node (ref "X-SOUTH") (pin "107") (pinfunction "107_107") (pintype "bidirectional"))
    )
    (net (code "208") (name "S31_P") (class "Default")
      (node (ref "SENSOR") (pin "B9") (pinfunction "OUT5_P_B9") (pintype "output"))
      (node (ref "X-SOUTH") (pin "105") (pinfunction "105_105") (pintype "bidirectional"))
    )
    (net (code "209") (name "S32_N") (class "Default")
      (node (ref "SENSOR") (pin "D9") (pinfunction "OUT6_N_D9") (pintype "output"))
      (node (ref "X-SOUTH") (pin "112") (pinfunction "112_112") (pintype "bidirectional"))
    )
    (net (code "210") (name "S32_P") (class "Default")
      (node (ref "SENSOR") (pin "D10") (pinfunction "OUT6_P_D10") (pintype "output"))
      (node (ref "X-SOUTH") (pin "110") (pinfunction "110_110") (pintype "bidirectional"))
    )
    (net (code "211") (name "S33_N") (class "Default")
      (node (ref "SENSOR") (pin "A7") (pinfunction "OUT2_N_A7") (pintype "output"))
      (node (ref "X-SOUTH") (pin "113") (pinfunction "113_113") (pintype "bidirectional"))
    )
    (net (code "212") (name "S33_P") (class "Default")
      (node (ref "SENSOR") (pin "A8") (pinfunction "OUT2_P_A8") (pintype "output"))
      (node (ref "X-SOUTH") (pin "111") (pinfunction "111_111") (pintype "bidirectional"))
    )
    (net (code "213") (name "S34_N") (class "Default")
      (node (ref "SENSOR") (pin "C7") (pinfunction "OUT4_N_C7") (pintype "output"))
      (node (ref "X-SOUTH") (pin "118") (pinfunction "118_118") (pintype "bidirectional"))
    )
    (net (code "214") (name "S34_P") (class "Default")
      (node (ref "SENSOR") (pin "C8") (pinfunction "OUT4_P_C8") (pintype "output"))
      (node (ref "X-SOUTH") (pin "116") (pinfunction "116_116") (pintype "bidirectional"))
    )
    (net (code "215") (name "S35_N") (class "Default")
      (node (ref "SENSOR") (pin "B6") (pinfunction "OUT1_N_B6") (pintype "output"))
      (node (ref "X-SOUTH") (pin "119") (pinfunction "119_119") (pintype "bidirectional"))
    )
    (net (code "216") (name "S35_P") (class "Default")
      (node (ref "SENSOR") (pin "B7") (pinfunction "OUT1_P_B7") (pintype "output"))
      (node (ref "X-SOUTH") (pin "117") (pinfunction "117_117") (pintype "bidirectional"))
    )
    (net (code "217") (name "S36_N") (class "Default")
      (node (ref "SENSOR") (pin "D7") (pinfunction "OUT3_N_D7") (pintype "output"))
      (node (ref "X-SOUTH") (pin "124") (pinfunction "124_124") (pintype "bidirectional"))
    )
    (net (code "218") (name "S36_P") (class "Default")
      (node (ref "SENSOR") (pin "D8") (pinfunction "OUT3_P_D8") (pintype "output"))
      (node (ref "X-SOUTH") (pin "122") (pinfunction "122_122") (pintype "bidirectional"))
    )
    (net (code "219") (name "S37_N") (class "Default")
      (node (ref "SENSOR") (pin "A5") (pinfunction "OUTCTR_N_A5") (pintype "output"))
      (node (ref "X-SOUTH") (pin "125") (pinfunction "125_125") (pintype "bidirectional"))
    )
    (net (code "220") (name "S37_P") (class "Default")
      (node (ref "SENSOR") (pin "A6") (pinfunction "OUTCTR_P_A6") (pintype "output"))
      (node (ref "X-SOUTH") (pin "123") (pinfunction "123_123") (pintype "bidirectional"))
    )
    (net (code "221") (name "S38_N") (class "Default")
      (node (ref "X-SOUTH") (pin "130") (pinfunction "130_130") (pintype "bidirectional"))
    )
    (net (code "222") (name "S38_P") (class "Default")
      (node (ref "X-SOUTH") (pin "128") (pinfunction "128_128") (pintype "bidirectional"))
    )
    (net (code "223") (name "S39_N") (class "Default")
      (node (ref "U3") (pin "6") (pinfunction "EN_6") (pintype "input"))
      (node (ref "X-SOUTH") (pin "131") (pinfunction "131_131") (pintype "bidirectional"))
    )
    (net (code "224") (name "S39_P") (class "Default")
      (node (ref "X-SOUTH") (pin "129") (pinfunction "129_129") (pintype "bidirectional"))
    )
    (net (code "225") (name "SPI_CLK") (class "Default")
      (node (ref "SENSOR") (pin "H29") (pinfunction "SPI_CLK_H29") (pintype "input"))
      (node (ref "U4") (pin "9") (pinfunction "B4_9") (pintype "bidirectional"))
    )
    (net (code "226") (name "SPI_EN") (class "Default")
      (node (ref "SENSOR") (pin "F28") (pinfunction "SPI_EN_F28") (pintype "input"))
      (node (ref "U4") (pin "12") (pinfunction "B1_12") (pintype "bidirectional"))
    )
    (net (code "227") (name "SPI_IN") (class "Default")
      (node (ref "SENSOR") (pin "E28") (pinfunction "SPI_IN_E28") (pintype "input"))
      (node (ref "U4") (pin "10") (pinfunction "B3_10") (pintype "bidirectional"))
    )
    (net (code "228") (name "SPI_OUT") (class "Default")
      (node (ref "SENSOR") (pin "G28") (pinfunction "SPI_OUT_G28") (pintype "output"))
      (node (ref "U4") (pin "11") (pinfunction "B2_11") (pintype "bidirectional"))
    )
    (net (code "229") (name "SYS_RES_N") (class "Default")
      (node (ref "SENSOR") (pin "F30") (pinfunction "SYS_RES_N_F30") (pintype "input"))
      (node (ref "U5") (pin "10") (pinfunction "B3_10") (pintype "bidirectional"))
    )
    (net (code "230") (name "S_CHK_EN") (class "Default")
      (node (ref "X-SOUTH") (pin "8") (pinfunction "8_8") (pintype "bidirectional"))
    )
    (net (code "231") (name "S_CHK_V") (class "Default")
      (node (ref "C5") (pin "1") (pinfunction "1_1") (pintype "passive"))
      (node (ref "C6") (pin "1") (pinfunction "1_1") (pintype "passive"))
      (node (ref "C7") (pin "1") (pinfunction "1_1") (pintype "passive"))
      (node (ref "R20") (pin "1") (pinfunction "1_1") (pintype "passive"))
      (node (ref "TP3") (pin "TP") (pinfunction "TP_TP") (pintype "input"))
      (node (ref "USE") (pin "8") (pinfunction "VDD_8") (pintype "power_in"))
      (node (ref "USS") (pin "8") (pinfunction "VDD_8") (pintype "power_in"))
      (node (ref "USW") (pin "8") (pinfunction "VDD_8") (pintype "power_in"))
      (node (ref "X-SOUTH") (pin "10") (pinfunction "10_10") (pintype "bidirectional"))
    )
    (net (code "232") (name "S_I2C_EN") (class "Default")
      (node (ref "X-SOUTH") (pin "137") (pinfunction "137_137") (pintype "bidirectional"))
    )
    (net (code "233") (name "S_I2C_V") (class "Default")
      (node (ref "U7") (pin "8") (pinfunction "VCC_8") (pintype "power_in"))
      (node (ref "X-SOUTH") (pin "135") (pinfunction "135_135") (pintype "bidirectional"))
    )
    (net (code "234") (name "S_REF") (class "Default")
      (node (ref "R20") (pin "2") (pinfunction "2_2") (pintype "passive"))
      (node (ref "TP4") (pin "TP") (pinfunction "TP_TP") (pintype "input"))
      (node (ref "U2") (pin "1") (pinfunction "CATHODE_1") (pintype "output"))
      (node (ref "U2") (pin "3") (pinfunction "REF_3") (pintype "input"))
      (node (ref "USE") (pin "2") (pinfunction "VINA-_2") (pintype "input"))
      (node (ref "USE") (pin "5") (pinfunction "VINB+_5") (pintype "input"))
      (node (ref "USS") (pin "2") (pinfunction "VINA-_2") (pintype "input"))
      (node (ref "USS") (pin "5") (pinfunction "VINB+_5") (pintype "input"))
      (node (ref "USW") (pin "2") (pinfunction "VINA-_2") (pintype "input"))
      (node (ref "USW") (pin "5") (pinfunction "VINB+_5") (pintype "input"))
    )
    (net (code "235") (name "S_SCK") (class "Default")
      (node (ref "X-SOUTH") (pin "144") (pinfunction "144_144") (pintype "bidirectional"))
    )
    (net (code "236") (name "S_SCL") (class "Default")
      (node (ref "U7") (pin "2") (pinfunction "SCL_2") (pintype "input"))
      (node (ref "X-SOUTH") (pin "143") (pinfunction "143_143") (pintype "bidirectional"))
    )
    (net (code "237") (name "S_SDA") (class "Default")
      (node (ref "U7") (pin "1") (pinfunction "SDA_1") (pintype "bidirectional"))
      (node (ref "X-SOUTH") (pin "141") (pinfunction "141_141") (pintype "bidirectional"))
    )
    (net (code "238") (name "S_SDI") (class "Default")
      (node (ref "X-SOUTH") (pin "140") (pinfunction "140_140") (pintype "bidirectional"))
    )
    (net (code "239") (name "S_SDO") (class "Default")
      (node (ref "X-SOUTH") (pin "142") (pinfunction "142_142") (pintype "bidirectional"))
    )
    (net (code "240") (name "S_SPI_EN") (class "Default")
      (node (ref "X-SOUTH") (pin "136") (pinfunction "136_136") (pintype "bidirectional"))
    )
    (net (code "241") (name "S_SPI_V") (class "Default")
      (node (ref "X-SOUTH") (pin "134") (pinfunction "134_134") (pintype "bidirectional"))
    )
    (net (code "242") (name "S_VE") (class "Default")
      (node (ref "X-SOUTH") (pin "13") (pinfunction "13_13") (pintype "bidirectional"))
      (node (ref "X-SOUTH") (pin "19") (pinfunction "19_19") (pintype "bidirectional"))
      (node (ref "X-SOUTH") (pin "25") (pinfunction "25_25") (pintype "bidirectional"))
      (node (ref "X-SOUTH") (pin "31") (pinfunction "31_31") (pintype "bidirectional"))
      (node (ref "X-SOUTH") (pin "37") (pinfunction "37_37") (pintype "bidirectional"))
    )
    (net (code "243") (name "S_VE_CV") (class "Default")
      (node (ref "C11") (pin "1") (pinfunction "1_1") (pintype "passive"))
      (node (ref "R10") (pin "1") (pinfunction "1_1") (pintype "passive"))
      (node (ref "X-SOUTH") (pin "2") (pinfunction "2_2") (pintype "bidirectional"))
    )
    (net (code "244") (name "S_VE_OV") (class "Default")
      (node (ref "USE") (pin "7") (pinfunction "OUTB_7") (pintype "output"))
      (node (ref "X-SOUTH") (pin "1") (pinfunction "1_1") (pintype "bidirectional"))
    )
    (net (code "245") (name "S_VE_UV") (class "Default")
      (node (ref "USE") (pin "1") (pinfunction "OUTA_1") (pintype "output"))
      (node (ref "X-SOUTH") (pin "7") (pinfunction "7_7") (pintype "bidirectional"))
    )
    (net (code "246") (name "S_VS") (class "Default")
      (node (ref "C45") (pin "1") (pinfunction "1_1") (pintype "passive"))
      (node (ref "C46") (pin "1") (pinfunction "1_1") (pintype "passive"))
      (node (ref "C47") (pin "1") (pinfunction "1_1") (pintype "passive"))
      (node (ref "C48") (pin "1") (pinfunction "1_1") (pintype "passive"))
      (node (ref "C49") (pin "1") (pinfunction "1_1") (pintype "passive"))
      (node (ref "C72") (pin "1") (pinfunction "1_1") (pintype "passive"))
      (node (ref "C73") (pin "1") (pinfunction "1_1") (pintype "passive"))
      (node (ref "C74") (pin "1") (pinfunction "1_1") (pintype "passive"))
      (node (ref "C81") (pin "1") (pinfunction "1_1") (pintype "passive"))
      (node (ref "C82") (pin "1") (pinfunction "1_1") (pintype "passive"))
      (node (ref "C83") (pin "1") (pinfunction "1_1") (pintype "passive"))
      (node (ref "SENSOR") (pin "A30") (pinfunction "VDD_PIX_A30") (pintype "power_in"))
      (node (ref "SENSOR") (pin "D28") (pinfunction "VDD_PIX_D28") (pintype "power_in"))
      (node (ref "SENSOR") (pin "D30") (pinfunction "VDD_PIX_D30") (pintype "power_in"))
      (node (ref "SENSOR") (pin "G1") (pinfunction "VDD_PIX_G1") (pintype "power_in"))
      (node (ref "SENSOR") (pin "H28") (pinfunction "VDD_PIX_H28") (pintype "power_in"))
      (node (ref "TP6") (pin "TP") (pinfunction "TP_TP") (pintype "input"))
      (node (ref "X-SOUTH") (pin "49") (pinfunction "49_49") (pintype "bidirectional"))
      (node (ref "X-SOUTH") (pin "55") (pinfunction "55_55") (pintype "bidirectional"))
      (node (ref "X-SOUTH") (pin "61") (pinfunction "61_61") (pintype "bidirectional"))
      (node (ref "X-SOUTH") (pin "67") (pinfunction "67_67") (pintype "bidirectional"))
      (node (ref "X-SOUTH") (pin "73") (pinfunction "73_73") (pintype "bidirectional"))
      (node (ref "X-SOUTH") (pin "79") (pinfunction "79_79") (pintype "bidirectional"))
      (node (ref "X-SOUTH") (pin "85") (pinfunction "85_85") (pintype "bidirectional"))
      (node (ref "X-SOUTH") (pin "91") (pinfunction "91_91") (pintype "bidirectional"))
      (node (ref "X-SOUTH") (pin "97") (pinfunction "97_97") (pintype "bidirectional"))
    )
    (net (code "247") (name "S_VS_CV") (class "Default")
      (node (ref "C12") (pin "1") (pinfunction "1_1") (pintype "passive"))
      (node (ref "R13") (pin "1") (pinfunction "1_1") (pintype "passive"))
      (node (ref "X-SOUTH") (pin "4") (pinfunction "4_4") (pintype "bidirectional"))
    )
    (net (code "248") (name "S_VS_OV") (class "Default")
      (node (ref "USS") (pin "7") (pinfunction "OUTB_7") (pintype "output"))
      (node (ref "X-SOUTH") (pin "3") (pinfunction "3_3") (pintype "bidirectional"))
    )
    (net (code "249") (name "S_VS_UV") (class "Default")
      (node (ref "USS") (pin "1") (pinfunction "OUTA_1") (pintype "output"))
      (node (ref "X-SOUTH") (pin "9") (pinfunction "9_9") (pintype "bidirectional"))
    )
    (net (code "250") (name "S_VW") (class "Default")
      (node (ref "C90") (pin "1") (pinfunction "1_1") (pintype "passive"))
      (node (ref "U3") (pin "1") (pinfunction "BIAS_1") (pintype "power_in"))
      (node (ref "U3") (pin "3") (pinfunction "IN_3") (pintype "power_in"))
      (node (ref "X-SOUTH") (pin "109") (pinfunction "109_109") (pintype "bidirectional"))
      (node (ref "X-SOUTH") (pin "115") (pinfunction "115_115") (pintype "bidirectional"))
      (node (ref "X-SOUTH") (pin "121") (pinfunction "121_121") (pintype "bidirectional"))
      (node (ref "X-SOUTH") (pin "127") (pinfunction "127_127") (pintype "bidirectional"))
      (node (ref "X-SOUTH") (pin "133") (pinfunction "133_133") (pintype "bidirectional"))
    )
    (net (code "251") (name "S_VW_CV") (class "Default")
      (node (ref "C13") (pin "1") (pinfunction "1_1") (pintype "passive"))
      (node (ref "R16") (pin "1") (pinfunction "1_1") (pintype "passive"))
      (node (ref "X-SOUTH") (pin "6") (pinfunction "6_6") (pintype "bidirectional"))
    )
    (net (code "252") (name "S_VW_OV") (class "Default")
      (node (ref "USW") (pin "7") (pinfunction "OUTB_7") (pintype "output"))
      (node (ref "X-SOUTH") (pin "5") (pinfunction "5_5") (pintype "bidirectional"))
    )
    (net (code "253") (name "S_VW_UV") (class "Default")
      (node (ref "USW") (pin "1") (pinfunction "OUTA_1") (pintype "output"))
      (node (ref "X-SOUTH") (pin "11") (pinfunction "11_11") (pintype "bidirectional"))
    )
    (net (code "254") (name "TDIG1") (class "Default")
      (node (ref "SENSOR") (pin "G27") (pinfunction "TDIG1_G27") (pintype "output"))
      (node (ref "U5") (pin "9") (pinfunction "B4_9") (pintype "bidirectional"))
    )
    (net (code "255") (name "TDIG2") (class "Default")
      (node (ref "SENSOR") (pin "G26") (pinfunction "TDIG2_G26") (pintype "output"))
      (node (ref "U6") (pin "11") (pinfunction "B2_11") (pintype "bidirectional"))
    )
    (net (code "256") (name "T_EXP1") (class "Default")
      (node (ref "SENSOR") (pin "H30") (pinfunction "T_EXP1_H30") (pintype "input"))
      (node (ref "U5") (pin "12") (pinfunction "B1_12") (pintype "bidirectional"))
    )
    (net (code "257") (name "T_EXP2") (class "Default")
      (node (ref "SENSOR") (pin "E29") (pinfunction "T_EXP2_E29") (pintype "input"))
      (node (ref "U6") (pin "10") (pinfunction "B3_10") (pintype "bidirectional"))
    )
    (net (code "258") (name "VRAMP1") (class "Default")
      (node (ref "C16") (pin "1") (pinfunction "1_1") (pintype "passive"))
      (node (ref "R23") (pin "1") (pinfunction "1_1") (pintype "passive"))
      (node (ref "SENSOR") (pin "G29") (pinfunction "VRAMP1_G29") (pintype "bidirectional"))
    )
    (net (code "259") (name "VRAMP2") (class "Default")
      (node (ref "C17") (pin "1") (pinfunction "1_1") (pintype "passive"))
      (node (ref "R23") (pin "2") (pinfunction "2_2") (pintype "passive"))
      (node (ref "SENSOR") (pin "F29") (pinfunction "VRAMP2_F29") (pintype "bidirectional"))
    )
    (net (code "260") (name "VTREF") (class "Default")
      (node (ref "C65") (pin "1") (pinfunction "1_1") (pintype "passive"))
      (node (ref "C91") (pin "2") (pinfunction "2_2") (pintype "passive"))
      (node (ref "R21") (pin "2") (pinfunction "2_2") (pintype "passive"))
      (node (ref "R24") (pin "1") (pinfunction "1_1") (pintype "passive"))
      (node (ref "SENSOR") (pin "B2") (pinfunction "VTREF_B2") (pintype "bidirectional"))
      (node (ref "U3") (pin "4") (pinfunction "OUT_4") (pintype "power_in"))
    )
    (net (code "261") (name "VTSIG") (class "Default")
      (node (ref "C66") (pin "1") (pinfunction "1_1") (pintype "passive"))
      (node (ref "R24") (pin "2") (pinfunction "2_2") (pintype "passive"))
      (node (ref "SENSOR") (pin "C2") (pinfunction "VTSIG_C2") (pintype "bidirectional"))
    )
    (net (code "262") (name "unconnected-(U1-NC-Pad2)") (class "Default")
      (node (ref "U1") (pin "2") (pinfunction "NC_2") (pintype "no_connect"))
    )
    (net (code "263") (name "unconnected-(U1-NC-Pad4)") (class "Default")
      (node (ref "U1") (pin "4") (pinfunction "NC_4") (pintype "no_connect"))
    )
    (net (code "264") (name "unconnected-(U1-NC-Pad5)") (class "Default")
      (node (ref "U1") (pin "5") (pinfunction "NC_5") (pintype "no_connect"))
    )
    (net (code "265") (name "unconnected-(U2-NC-Pad2)") (class "Default")
      (node (ref "U2") (pin "2") (pinfunction "NC_2") (pintype "no_connect"))
    )
    (net (code "266") (name "unconnected-(U2-NC-Pad4)") (class "Default")
      (node (ref "U2") (pin "4") (pinfunction "NC_4") (pintype "no_connect"))
    )
    (net (code "267") (name "unconnected-(U2-NC-Pad5)") (class "Default")
      (node (ref "U2") (pin "5") (pinfunction "NC_5") (pintype "no_connect"))
    )
    (net (code "268") (name "unconnected-(U7-OS-Pad3)") (class "Default")
      (node (ref "U7") (pin "3") (pinfunction "OS_3") (pintype "output"))
    )
    (net (code "269") (name "unconnected-(X-NORTH-PadM1)") (class "Default")
      (node (ref "X-NORTH") (pin "M1") (pinfunction "M1_M1") (pintype "bidirectional"))
    )
    (net (code "270") (name "unconnected-(X-NORTH-PadM2)") (class "Default")
      (node (ref "X-NORTH") (pin "M2") (pinfunction "M2_M2") (pintype "bidirectional"))
    )
    (net (code "271") (name "unconnected-(X-SOUTH-PadM1)") (class "Default")
      (node (ref "X-SOUTH") (pin "M1") (pinfunction "M1_M1") (pintype "bidirectional"))
    )
    (net (code "272") (name "unconnected-(X-SOUTH-PadM2)") (class "Default")
      (node (ref "X-SOUTH") (pin "M2") (pinfunction "M2_M2") (pintype "bidirectional"))
    )
  )
)
